# EEZ_DIB_DCM220_r2B3.net
KiCad netlist of a schematic drawn in EAGLE
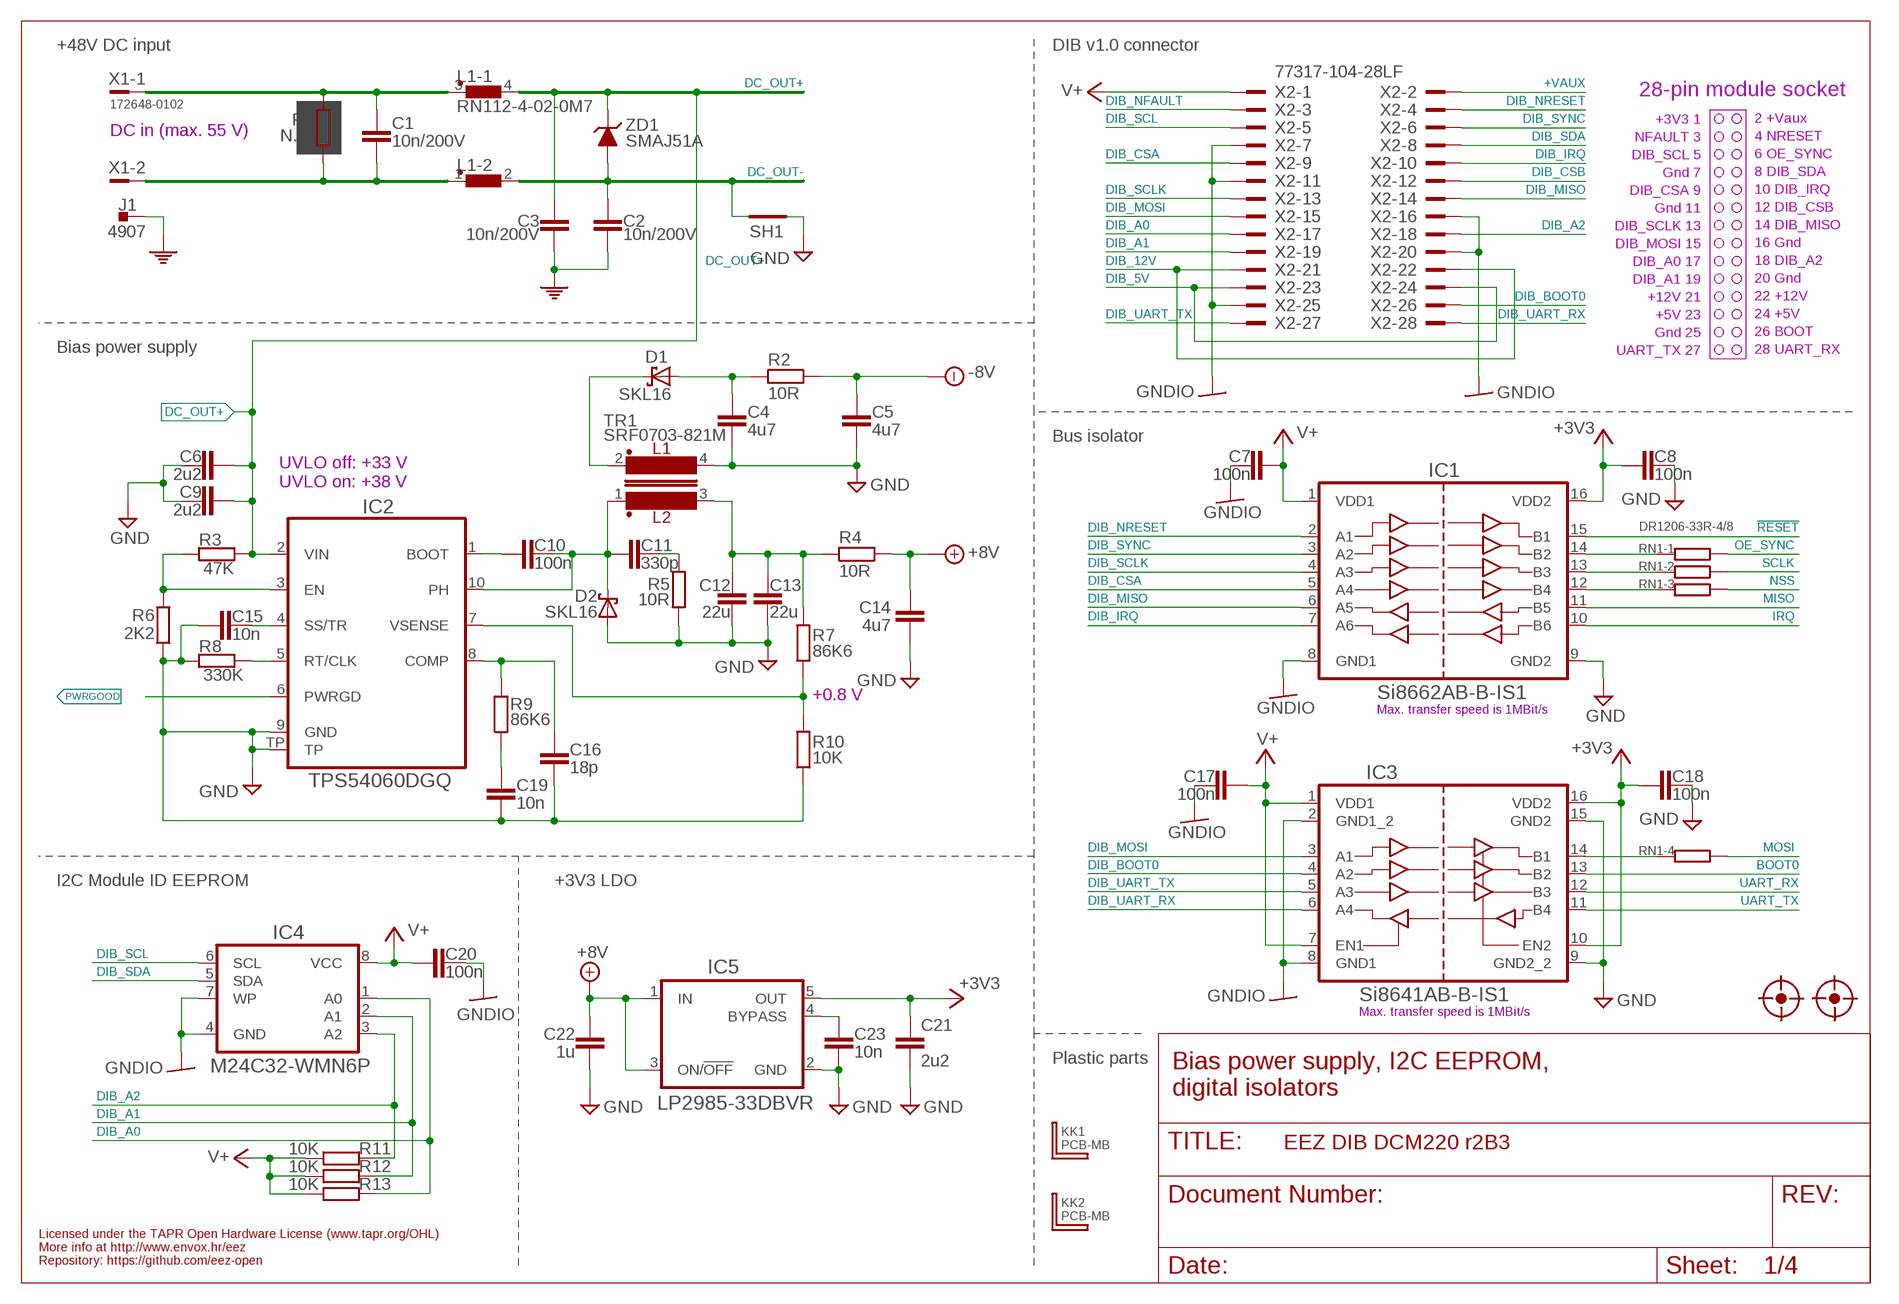
[diagram p0: schematic, sheet 1]
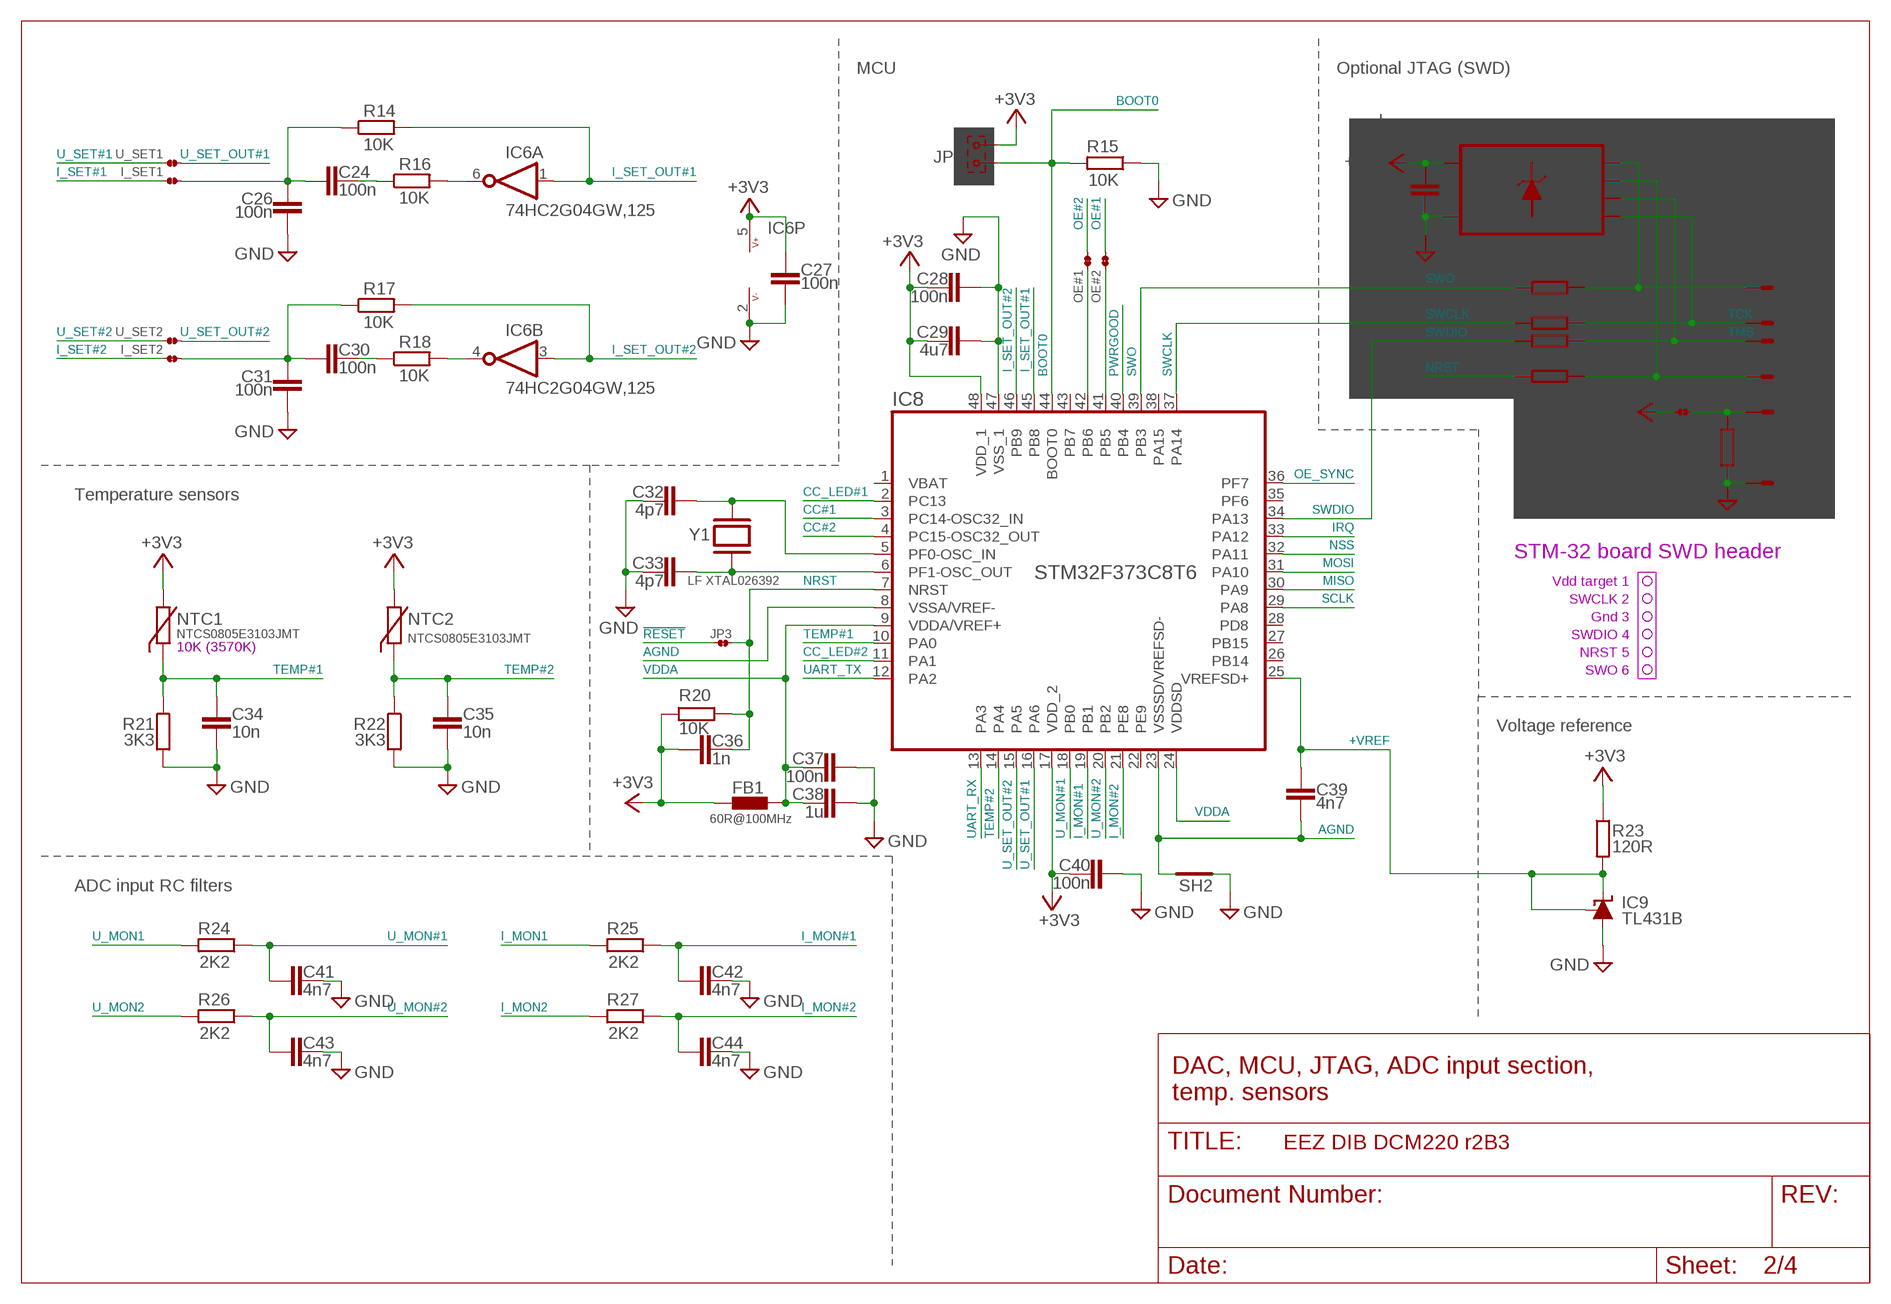
[diagram p1: schematic, sheet 2]
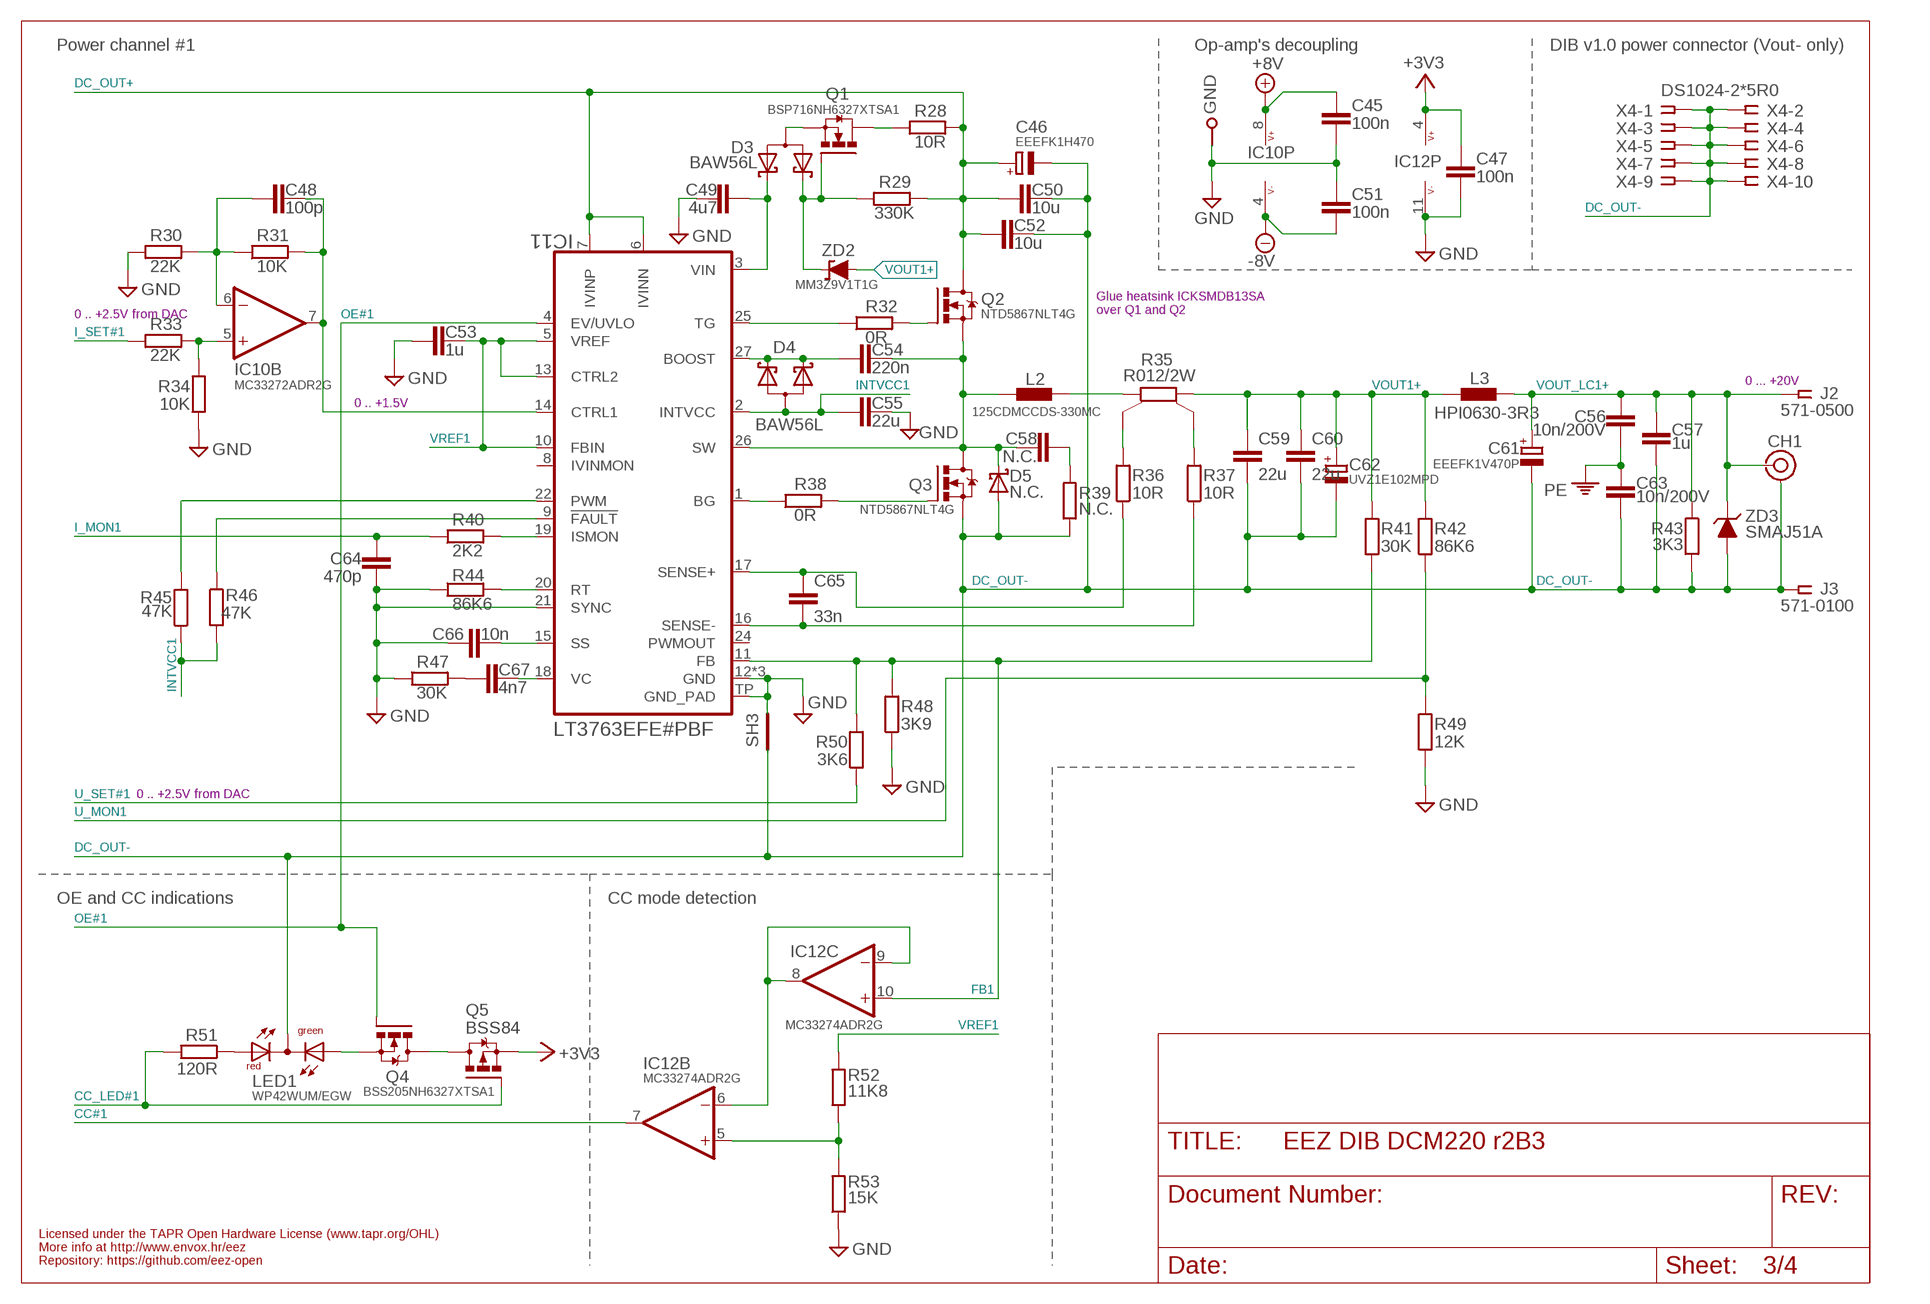
[diagram p2: schematic, sheet 3]
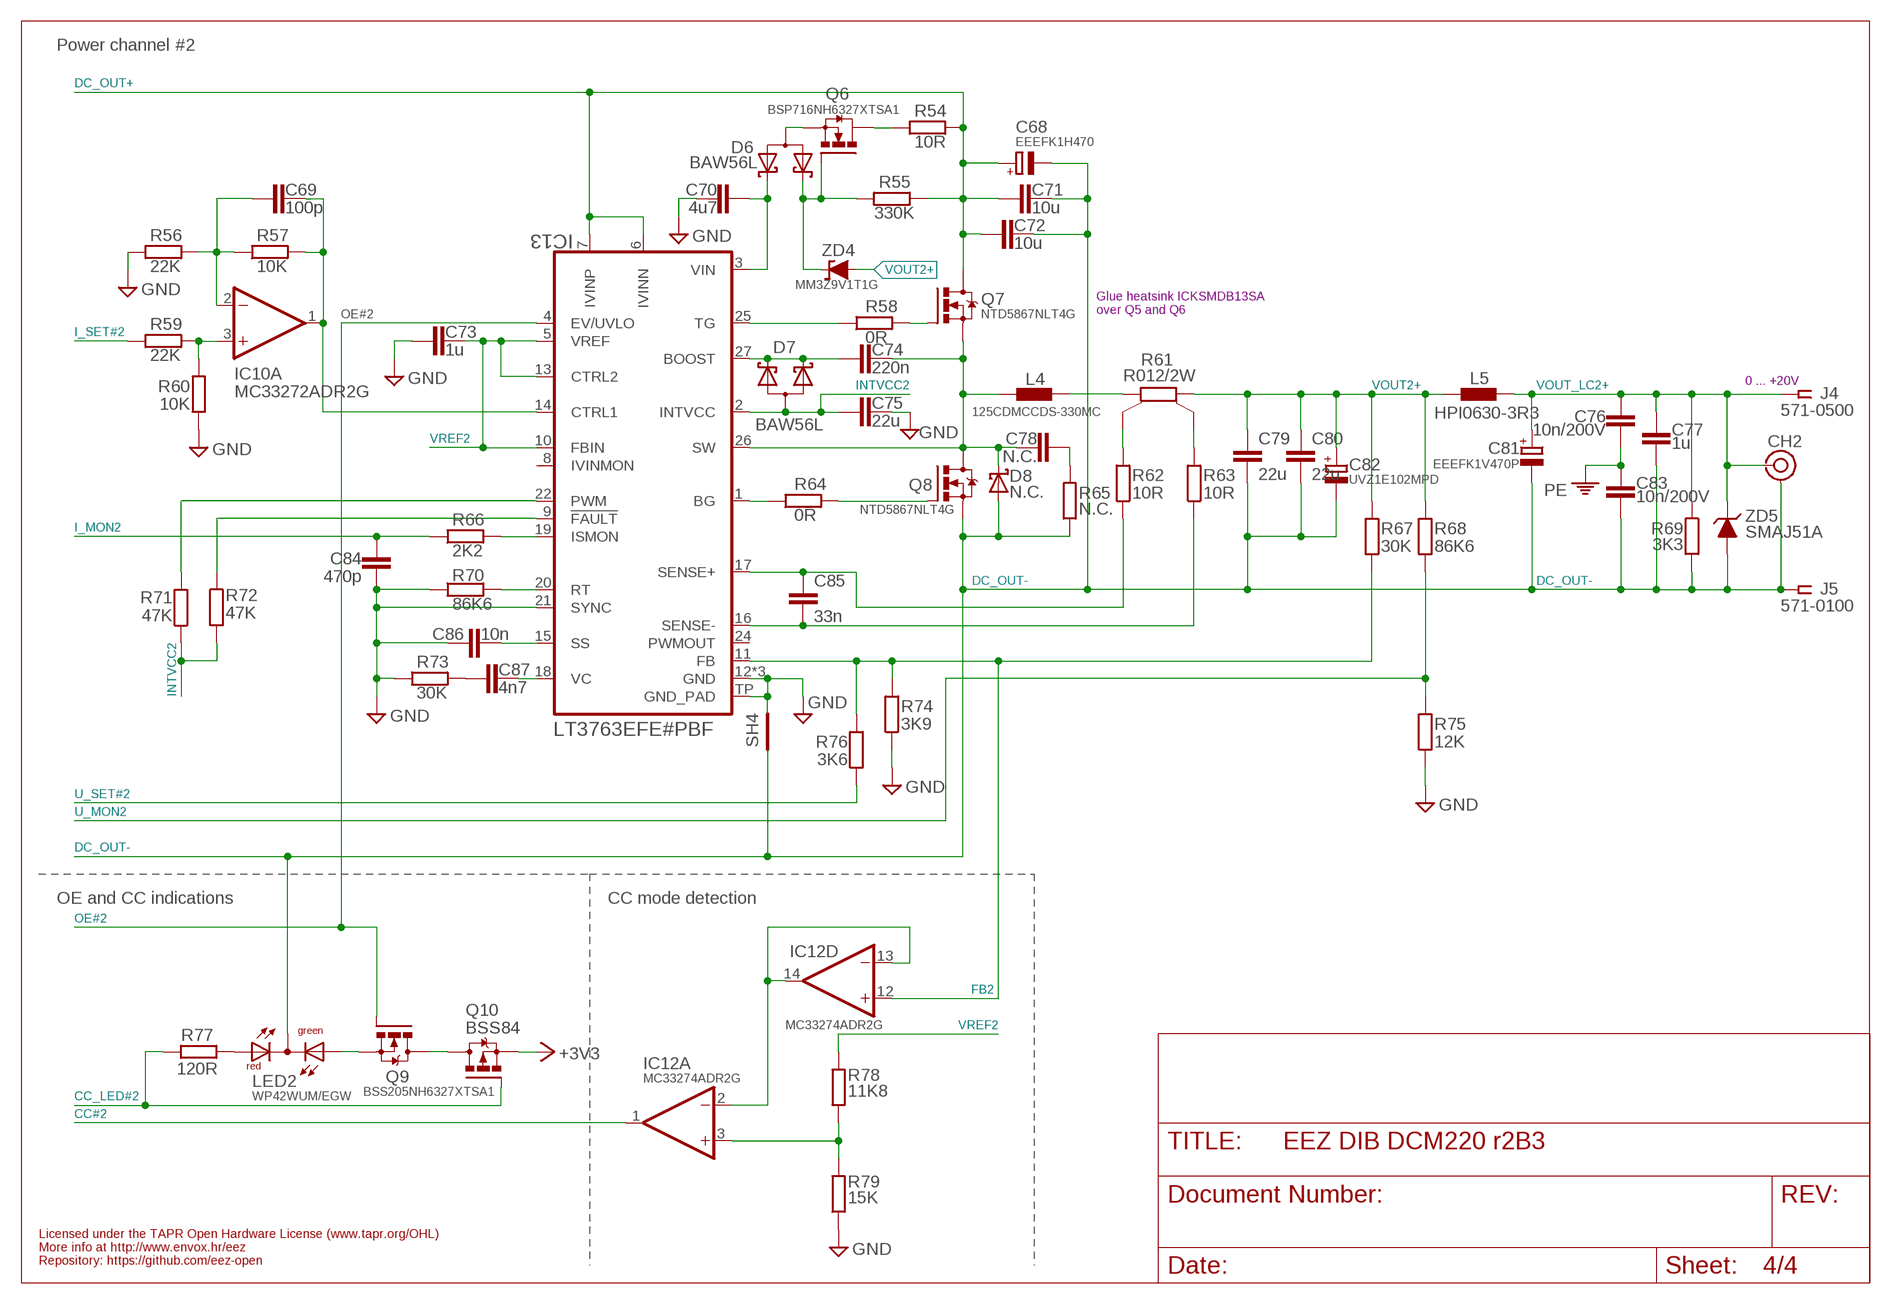
[diagram p3: schematic, sheet 4]

(export (version "E")
  (design (tool "Eeschema 10.0.6"))
  (components
    (comp (ref "C45")
      (value "100n")
      (footprint "eagle-import:C0603")
      (libsource (lib "eagle-import") (part "C-EUC0603"))
    )
    (comp (ref "C46")
      (value "EEEFK1H470")
      (footprint "eagle-import:CAPAE830X1050N")
      (libsource (lib "eagle-import") (part "ECAPSMD8.3MM/HA0"))
    )
    (comp (ref "C47")
      (value "100n")
      (footprint "eagle-import:C0603")
      (libsource (lib "eagle-import") (part "C-EUC0603"))
    )
    (comp (ref "C48")
      (value "100p")
      (footprint "eagle-import:C0805")
      (libsource (lib "eagle-import") (part "C-EUC0805"))
    )
    (comp (ref "C49")
      (value "4u7")
      (footprint "eagle-import:C1206")
      (libsource (lib "eagle-import") (part "C-EUC1206"))
    )
    (comp (ref "C50")
      (value "10u")
      (footprint "eagle-import:C1210")
      (libsource (lib "eagle-import") (part "C-EUC1210"))
    )
    (comp (ref "C51")
      (value "100n")
      (footprint "eagle-import:C0603")
      (libsource (lib "eagle-import") (part "C-EUC0603"))
    )
    (comp (ref "C52")
      (value "10u")
      (footprint "eagle-import:C1210")
      (libsource (lib "eagle-import") (part "C-EUC1210"))
    )
    (comp (ref "C53")
      (value "1u")
      (footprint "eagle-import:C0805")
      (libsource (lib "eagle-import") (part "C-EUC0805"))
    )
    (comp (ref "C54")
      (value "220n")
      (footprint "eagle-import:C0805")
      (libsource (lib "eagle-import") (part "C-EUC0805"))
    )
    (comp (ref "C55")
      (value "22u")
      (footprint "eagle-import:C1210")
      (libsource (lib "eagle-import") (part "C-EUC1210"))
    )
    (comp (ref "C56")
      (value "10n/200V")
      (footprint "eagle-import:C1206")
      (libsource (lib "eagle-import") (part "C-EUC1206"))
    )
    (comp (ref "C57")
      (value "1u")
      (footprint "eagle-import:C0805")
      (libsource (lib "eagle-import") (part "C-EUC0805"))
    )
    (comp (ref "C58")
      (value "N.C.")
      (footprint "eagle-import:C0805")
      (libsource (lib "eagle-import") (part "C-EUC0805"))
    )
    (comp (ref "C59")
      (value "22u")
      (footprint "eagle-import:C1210")
      (libsource (lib "eagle-import") (part "C-EUC1210"))
    )
    (comp (ref "C60")
      (value "22u")
      (footprint "eagle-import:C1210")
      (libsource (lib "eagle-import") (part "C-EUC1210"))
    )
    (comp (ref "C61")
      (value "EEEFK1V470P")
      (footprint "eagle-import:CAPAE660X610N")
      (libsource (lib "eagle-import") (part "ECAPPANASONIC_H"))
    )
    (comp (ref "C62")
      (value "UVZ1E102MPD")
      (footprint "eagle-import:ECAP5_10.5")
      (libsource (lib "eagle-import") (part "ECAP5G_10.5MM"))
    )
    (comp (ref "C63")
      (value "10n/200V")
      (footprint "eagle-import:C1206")
      (libsource (lib "eagle-import") (part "C-EUC1206"))
    )
    (comp (ref "C64")
      (value "470p")
      (footprint "eagle-import:C0805")
      (libsource (lib "eagle-import") (part "C-EUC0805"))
    )
    (comp (ref "C65")
      (value "33n")
      (footprint "eagle-import:C0805")
      (libsource (lib "eagle-import") (part "C-EUC0805"))
    )
    (comp (ref "C66")
      (value "10n")
      (footprint "eagle-import:C0805")
      (libsource (lib "eagle-import") (part "C-EUC0805"))
    )
    (comp (ref "C67")
      (value "4n7")
      (footprint "eagle-import:C0805")
      (libsource (lib "eagle-import") (part "C-EUC0805"))
    )
    (comp (ref "CH1")
      (value "TEST_POINT-2")
      (footprint "eagle-import:TP_1.1MM_2")
      (libsource (lib "eagle-import") (part "TEST_POINT-2"))
    )
    (comp (ref "D3")
      (value "BAW56L")
      (footprint "eagle-import:SOT23")
      (libsource (lib "eagle-import") (part "BAW56L"))
    )
    (comp (ref "D4")
      (value "BAW56L")
      (footprint "eagle-import:SOT23")
      (libsource (lib "eagle-import") (part "BAW56L"))
    )
    (comp (ref "D5")
      (value "N.C.")
      (footprint "eagle-import:SMA")
      (libsource (lib "eagle-import") (part "SCHOTTKYSMA_DO-214AC"))
    )
    (comp (ref "GND")
      (value "TEST-PIN_0.9MM")
      (footprint "eagle-import:TEST-PIN_0.9MM")
      (libsource (lib "eagle-import") (part "TEST-PIN_0.9MM"))
    )
    (comp (ref "IC10")
      (value "MC33272ADR2G")
      (footprint "eagle-import:SOIC127P600X173-8N")
      (libsource (lib "eagle-import") (part "TL072SOIC8"))
    )
    (comp (ref "IC11")
      (value "LT3763EFE#PBF")
      (footprint "eagle-import:LTC_05-08-1663-EB")
      (libsource (lib "eagle-import") (part "LT3763EFE#PBF"))
    )
    (comp (ref "IC12")
      (value "MC33274ADR2G")
      (footprint "eagle-import:SOIC127P600X175-14N")
      (fields (field (name "MPN") "TL074ACD"))
      (libsource (lib "eagle-import") (part "TL074SOIC14"))
    )
    (comp (ref "J2")
      (value "571-0500")
      (footprint "eagle-import:DELTRON_571")
      (libsource (lib "eagle-import") (part "571-0500"))
    )
    (comp (ref "J3")
      (value "571-0100")
      (footprint "eagle-import:DELTRON_571")
      (libsource (lib "eagle-import") (part "571-0100"))
    )
    (comp (ref "L2")
      (value "125CDMCCDS-330MC")
      (footprint "eagle-import:125CDMCC_DS")
      (libsource (lib "eagle-import") (part "125CDMCC/DS"))
    )
    (comp (ref "L3")
      (value "HPI0630-3R3")
      (footprint "eagle-import:COILCRAFT_HPI0630")
      (libsource (lib "eagle-import") (part "COILCRAFT_HPI0630"))
    )
    (comp (ref "LED1")
      (value "WP42WUM/EGW")
      (footprint "eagle-import:L-42WUM-1EGWT")
      (libsource (lib "eagle-import") (part "LED_L-42WUM/1EGWT"))
    )
    (comp (ref "Q1")
      (value "BSP716NH6327XTSA1")
      (footprint "eagle-import:SOT223")
      (libsource (lib "eagle-import") (part "N-HEXFET-2D_?-SOT232IRLL014N"))
    )
    (comp (ref "Q2")
      (value "NTD5867NLT4G")
      (footprint "eagle-import:TO229P990X239-3N")
      (libsource (lib "eagle-import") (part "N-MOSFETDPAK"))
    )
    (comp (ref "Q3")
      (value "NTD5867NLT4G")
      (footprint "eagle-import:TO229P990X239-3N")
      (libsource (lib "eagle-import") (part "N-MOSFETDPAK"))
    )
    (comp (ref "Q4")
      (value "BSS205NH6327XTSA1")
      (footprint "eagle-import:SOT103P240X110-3N")
      (fields (field (name "MPN") "2N7002-7-F"))
      (libsource (lib "eagle-import") (part "2N7002"))
    )
    (comp (ref "Q5")
      (value "BSS84")
      (footprint "eagle-import:SOT95P237X112-3N")
      (fields (field (name "MPN") "IRLML2246TRPBF"))
      (libsource (lib "eagle-import") (part "IRLML2246TRPBF"))
    )
    (comp (ref "R28")
      (value "10R")
      (footprint "eagle-import:R0805")
      (libsource (lib "eagle-import") (part "R-EU_R0805"))
    )
    (comp (ref "R29")
      (value "330K")
      (footprint "eagle-import:R0805")
      (libsource (lib "eagle-import") (part "R-EU_R0805"))
    )
    (comp (ref "R30")
      (value "22K")
      (footprint "eagle-import:R0805")
      (libsource (lib "eagle-import") (part "R-EU_R0805"))
    )
    (comp (ref "R31")
      (value "10K")
      (footprint "eagle-import:R0805")
      (libsource (lib "eagle-import") (part "R-EU_R0805"))
    )
    (comp (ref "R32")
      (value "0R")
      (footprint "eagle-import:R0805")
      (libsource (lib "eagle-import") (part "R-EU_R0805"))
    )
    (comp (ref "R33")
      (value "22K")
      (footprint "eagle-import:R0805")
      (libsource (lib "eagle-import") (part "R-EU_R0805"))
    )
    (comp (ref "R34")
      (value "10K")
      (footprint "eagle-import:R0805")
      (libsource (lib "eagle-import") (part "R-EU_R0805"))
    )
    (comp (ref "R35")
      (value "R012/2W")
      (footprint "eagle-import:R_2512-4WIRE")
      (libsource (lib "eagle-import") (part "R-EU_4WIRE2512"))
    )
    (comp (ref "R36")
      (value "10R")
      (footprint "eagle-import:R0805")
      (libsource (lib "eagle-import") (part "R-EU_R0805"))
    )
    (comp (ref "R37")
      (value "10R")
      (footprint "eagle-import:R0805")
      (libsource (lib "eagle-import") (part "R-EU_R0805"))
    )
    (comp (ref "R38")
      (value "0R")
      (footprint "eagle-import:R0805")
      (libsource (lib "eagle-import") (part "R-EU_R0805"))
    )
    (comp (ref "R39")
      (value "N.C.")
      (footprint "eagle-import:R1206")
      (libsource (lib "eagle-import") (part "R-EU_R1206"))
    )
    (comp (ref "R40")
      (value "2K2")
      (footprint "eagle-import:R0805")
      (libsource (lib "eagle-import") (part "R-EU_R0805"))
    )
    (comp (ref "R41")
      (value "30K")
      (footprint "eagle-import:R0805")
      (libsource (lib "eagle-import") (part "R-EU_R0805"))
    )
    (comp (ref "R42")
      (value "86K6")
      (footprint "eagle-import:R0805")
      (libsource (lib "eagle-import") (part "R-EU_R0805"))
    )
    (comp (ref "R43")
      (value "3K3")
      (footprint "eagle-import:R0805")
      (libsource (lib "eagle-import") (part "R-EU_R0805"))
    )
    (comp (ref "R44")
      (value "86K6")
      (footprint "eagle-import:R0805")
      (libsource (lib "eagle-import") (part "R-EU_R0805"))
    )
    (comp (ref "R45")
      (value "47K")
      (footprint "eagle-import:R0805")
      (libsource (lib "eagle-import") (part "R-EU_R0805"))
    )
    (comp (ref "R46")
      (value "47K")
      (footprint "eagle-import:R0805")
      (libsource (lib "eagle-import") (part "R-EU_R0805"))
    )
    (comp (ref "R47")
      (value "30K")
      (footprint "eagle-import:R0805")
      (libsource (lib "eagle-import") (part "R-EU_R0805"))
    )
    (comp (ref "R48")
      (value "3K9")
      (footprint "eagle-import:R0805")
      (libsource (lib "eagle-import") (part "R-EU_R0805"))
    )
    (comp (ref "R49")
      (value "12K")
      (footprint "eagle-import:R0805")
      (libsource (lib "eagle-import") (part "R-EU_R0805"))
    )
    (comp (ref "R50")
      (value "3K6")
      (footprint "eagle-import:R0805")
      (libsource (lib "eagle-import") (part "R-EU_R0805"))
    )
    (comp (ref "R51")
      (value "120R")
      (footprint "eagle-import:R0805")
      (libsource (lib "eagle-import") (part "R-EU_R0805"))
    )
    (comp (ref "R52")
      (value "11K8")
      (footprint "eagle-import:R0805")
      (libsource (lib "eagle-import") (part "R-EU_R0805"))
    )
    (comp (ref "R53")
      (value "15K")
      (footprint "eagle-import:R0805")
      (libsource (lib "eagle-import") (part "R-EU_R0805"))
    )
    (comp (ref "SH3")
      (value "SHORTNOHOLE")
      (footprint "eagle-import:SHORT_NOHOLE")
      (libsource (lib "eagle-import") (part "SHORTNOHOLE"))
    )
    (comp (ref "X4")
      (value "DS1024-2*5R0")
      (footprint "eagle-import:SSW-105-02-T-D-RA")
      (libsource (lib "eagle-import") (part "SSW-105-02-T-D-RA"))
    )
    (comp (ref "ZD2")
      (value "MM3Z9V1T1G")
      (footprint "eagle-import:SOD323-W")
      (libsource (lib "eagle-import") (part "ZENER-DIODESOD323"))
    )
    (comp (ref "ZD3")
      (value "SMAJ51A")
      (footprint "eagle-import:DO214AA")
      (libsource (lib "eagle-import") (part "P6SMB68A"))
    )
    (comp (ref "C68")
      (value "EEEFK1H470")
      (footprint "eagle-import:CAPAE830X1050N")
      (libsource (lib "eagle-import") (part "ECAPSMD8.3MM/HA0"))
    )
    (comp (ref "C69")
      (value "100p")
      (footprint "eagle-import:C0805")
      (libsource (lib "eagle-import") (part "C-EUC0805"))
    )
    (comp (ref "C70")
      (value "4u7")
      (footprint "eagle-import:C1206")
      (libsource (lib "eagle-import") (part "C-EUC1206"))
    )
    (comp (ref "C71")
      (value "10u")
      (footprint "eagle-import:C1210")
      (libsource (lib "eagle-import") (part "C-EUC1210"))
    )
    (comp (ref "C72")
      (value "10u")
      (footprint "eagle-import:C1210")
      (libsource (lib "eagle-import") (part "C-EUC1210"))
    )
    (comp (ref "C73")
      (value "1u")
      (footprint "eagle-import:C0805")
      (libsource (lib "eagle-import") (part "C-EUC0805"))
    )
    (comp (ref "C74")
      (value "220n")
      (footprint "eagle-import:C0805")
      (libsource (lib "eagle-import") (part "C-EUC0805"))
    )
    (comp (ref "C75")
      (value "22u")
      (footprint "eagle-import:C1210")
      (libsource (lib "eagle-import") (part "C-EUC1210"))
    )
    (comp (ref "C76")
      (value "10n/200V")
      (footprint "eagle-import:C1206")
      (libsource (lib "eagle-import") (part "C-EUC1206"))
    )
    (comp (ref "C77")
      (value "1u")
      (footprint "eagle-import:C0805")
      (libsource (lib "eagle-import") (part "C-EUC0805"))
    )
    (comp (ref "C78")
      (value "N.C.")
      (footprint "eagle-import:C0805")
      (libsource (lib "eagle-import") (part "C-EUC0805"))
    )
    (comp (ref "C79")
      (value "22u")
      (footprint "eagle-import:C1210")
      (libsource (lib "eagle-import") (part "C-EUC1210"))
    )
    (comp (ref "C80")
      (value "22u")
      (footprint "eagle-import:C1210")
      (libsource (lib "eagle-import") (part "C-EUC1210"))
    )
    (comp (ref "C81")
      (value "EEEFK1V470P")
      (footprint "eagle-import:CAPAE660X610N")
      (libsource (lib "eagle-import") (part "ECAPPANASONIC_H"))
    )
    (comp (ref "C82")
      (value "UVZ1E102MPD")
      (footprint "eagle-import:ECAP5_10.5")
      (libsource (lib "eagle-import") (part "ECAP5G_10.5MM"))
    )
    (comp (ref "C83")
      (value "10n/200V")
      (footprint "eagle-import:C1206")
      (libsource (lib "eagle-import") (part "C-EUC1206"))
    )
    (comp (ref "C84")
      (value "470p")
      (footprint "eagle-import:C0805")
      (libsource (lib "eagle-import") (part "C-EUC0805"))
    )
    (comp (ref "C85")
      (value "33n")
      (footprint "eagle-import:C0805")
      (libsource (lib "eagle-import") (part "C-EUC0805"))
    )
    (comp (ref "C86")
      (value "10n")
      (footprint "eagle-import:C0805")
      (libsource (lib "eagle-import") (part "C-EUC0805"))
    )
    (comp (ref "C87")
      (value "4n7")
      (footprint "eagle-import:C0805")
      (libsource (lib "eagle-import") (part "C-EUC0805"))
    )
    (comp (ref "CH2")
      (value "TEST_POINT-2")
      (footprint "eagle-import:TP_1.1MM_2")
      (libsource (lib "eagle-import") (part "TEST_POINT-2"))
    )
    (comp (ref "D6")
      (value "BAW56L")
      (footprint "eagle-import:SOT23")
      (libsource (lib "eagle-import") (part "BAW56L"))
    )
    (comp (ref "D7")
      (value "BAW56L")
      (footprint "eagle-import:SOT23")
      (libsource (lib "eagle-import") (part "BAW56L"))
    )
    (comp (ref "D8")
      (value "N.C.")
      (footprint "eagle-import:SMA")
      (libsource (lib "eagle-import") (part "SCHOTTKYSMA_DO-214AC"))
    )
    (comp (ref "IC13")
      (value "LT3763EFE#PBF")
      (footprint "eagle-import:LTC_05-08-1663-EB")
      (libsource (lib "eagle-import") (part "LT3763EFE#PBF"))
    )
    (comp (ref "J4")
      (value "571-0500")
      (footprint "eagle-import:DELTRON_571")
      (libsource (lib "eagle-import") (part "571-0500"))
    )
    (comp (ref "J5")
      (value "571-0100")
      (footprint "eagle-import:DELTRON_571")
      (libsource (lib "eagle-import") (part "571-0100"))
    )
    (comp (ref "L4")
      (value "125CDMCCDS-330MC")
      (footprint "eagle-import:125CDMCC_DS")
      (libsource (lib "eagle-import") (part "125CDMCC/DS"))
    )
    (comp (ref "L5")
      (value "HPI0630-3R3")
      (footprint "eagle-import:COILCRAFT_HPI0630")
      (libsource (lib "eagle-import") (part "COILCRAFT_HPI0630"))
    )
    (comp (ref "LED2")
      (value "WP42WUM/EGW")
      (footprint "eagle-import:L-42WUM-1EGWT")
      (libsource (lib "eagle-import") (part "LED_L-42WUM/1EGWT"))
    )
    (comp (ref "Q6")
      (value "BSP716NH6327XTSA1")
      (footprint "eagle-import:SOT223")
      (libsource (lib "eagle-import") (part "N-HEXFET-2D_?-SOT232IRLL014N"))
    )
    (comp (ref "Q7")
      (value "NTD5867NLT4G")
      (footprint "eagle-import:TO229P990X239-3N")
      (libsource (lib "eagle-import") (part "N-MOSFETDPAK"))
    )
    (comp (ref "Q8")
      (value "NTD5867NLT4G")
      (footprint "eagle-import:TO229P990X239-3N")
      (libsource (lib "eagle-import") (part "N-MOSFETDPAK"))
    )
    (comp (ref "Q9")
      (value "BSS205NH6327XTSA1")
      (footprint "eagle-import:SOT103P240X110-3N")
      (fields (field (name "MPN") "2N7002-7-F"))
      (libsource (lib "eagle-import") (part "2N7002"))
    )
    (comp (ref "Q10")
      (value "BSS84")
      (footprint "eagle-import:SOT95P237X112-3N")
      (fields (field (name "MPN") "IRLML2246TRPBF"))
      (libsource (lib "eagle-import") (part "IRLML2246TRPBF"))
    )
    (comp (ref "R54")
      (value "10R")
      (footprint "eagle-import:R0805")
      (libsource (lib "eagle-import") (part "R-EU_R0805"))
    )
    (comp (ref "R55")
      (value "330K")
      (footprint "eagle-import:R0805")
      (libsource (lib "eagle-import") (part "R-EU_R0805"))
    )
    (comp (ref "R56")
      (value "22K")
      (footprint "eagle-import:R0805")
      (libsource (lib "eagle-import") (part "R-EU_R0805"))
    )
    (comp (ref "R57")
      (value "10K")
      (footprint "eagle-import:R0805")
      (libsource (lib "eagle-import") (part "R-EU_R0805"))
    )
    (comp (ref "R58")
      (value "0R")
      (footprint "eagle-import:R0805")
      (libsource (lib "eagle-import") (part "R-EU_R0805"))
    )
    (comp (ref "R59")
      (value "22K")
      (footprint "eagle-import:R0805")
      (libsource (lib "eagle-import") (part "R-EU_R0805"))
    )
    (comp (ref "R60")
      (value "10K")
      (footprint "eagle-import:R0805")
      (libsource (lib "eagle-import") (part "R-EU_R0805"))
    )
    (comp (ref "R61")
      (value "R012/2W")
      (footprint "eagle-import:R_2512-4WIRE")
      (libsource (lib "eagle-import") (part "R-EU_4WIRE2512"))
    )
    (comp (ref "R62")
      (value "10R")
      (footprint "eagle-import:R0805")
      (libsource (lib "eagle-import") (part "R-EU_R0805"))
    )
    (comp (ref "R63")
      (value "10R")
      (footprint "eagle-import:R0805")
      (libsource (lib "eagle-import") (part "R-EU_R0805"))
    )
    (comp (ref "R64")
      (value "0R")
      (footprint "eagle-import:R0805")
      (libsource (lib "eagle-import") (part "R-EU_R0805"))
    )
    (comp (ref "R65")
      (value "N.C.")
      (footprint "eagle-import:R1206")
      (libsource (lib "eagle-import") (part "R-EU_R1206"))
    )
    (comp (ref "R66")
      (value "2K2")
      (footprint "eagle-import:R0805")
      (libsource (lib "eagle-import") (part "R-EU_R0805"))
    )
    (comp (ref "R67")
      (value "30K")
      (footprint "eagle-import:R0805")
      (libsource (lib "eagle-import") (part "R-EU_R0805"))
    )
    (comp (ref "R68")
      (value "86K6")
      (footprint "eagle-import:R0805")
      (libsource (lib "eagle-import") (part "R-EU_R0805"))
    )
    (comp (ref "R69")
      (value "3K3")
      (footprint "eagle-import:R0805")
      (libsource (lib "eagle-import") (part "R-EU_R0805"))
    )
    (comp (ref "R70")
      (value "86K6")
      (footprint "eagle-import:R0805")
      (libsource (lib "eagle-import") (part "R-EU_R0805"))
    )
    (comp (ref "R71")
      (value "47K")
      (footprint "eagle-import:R0805")
      (libsource (lib "eagle-import") (part "R-EU_R0805"))
    )
    (comp (ref "R72")
      (value "47K")
      (footprint "eagle-import:R0805")
      (libsource (lib "eagle-import") (part "R-EU_R0805"))
    )
    (comp (ref "R73")
      (value "30K")
      (footprint "eagle-import:R0805")
      (libsource (lib "eagle-import") (part "R-EU_R0805"))
    )
    (comp (ref "R74")
      (value "3K9")
      (footprint "eagle-import:R0805")
      (libsource (lib "eagle-import") (part "R-EU_R0805"))
    )
    (comp (ref "R75")
      (value "12K")
      (footprint "eagle-import:R0805")
      (libsource (lib "eagle-import") (part "R-EU_R0805"))
    )
    (comp (ref "R76")
      (value "3K6")
      (footprint "eagle-import:R0805")
      (libsource (lib "eagle-import") (part "R-EU_R0805"))
    )
    (comp (ref "R77")
      (value "120R")
      (footprint "eagle-import:R0805")
      (libsource (lib "eagle-import") (part "R-EU_R0805"))
    )
    (comp (ref "R78")
      (value "11K8")
      (footprint "eagle-import:R0805")
      (libsource (lib "eagle-import") (part "R-EU_R0805"))
    )
    (comp (ref "R79")
      (value "15K")
      (footprint "eagle-import:R0805")
      (libsource (lib "eagle-import") (part "R-EU_R0805"))
    )
    (comp (ref "SH4")
      (value "SHORTNOHOLE")
      (footprint "eagle-import:SHORT_NOHOLE")
      (libsource (lib "eagle-import") (part "SHORTNOHOLE"))
    )
    (comp (ref "ZD4")
      (value "MM3Z9V1T1G")
      (footprint "eagle-import:SOD323-W")
      (libsource (lib "eagle-import") (part "ZENER-DIODESOD323"))
    )
    (comp (ref "ZD5")
      (value "SMAJ51A")
      (footprint "eagle-import:DO214AA")
      (libsource (lib "eagle-import") (part "P6SMB68A"))
    )
    (comp (ref "C24")
      (value "100n")
      (footprint "eagle-import:C0603")
      (libsource (lib "eagle-import") (part "C-EUC0603"))
    )
    (comp (ref "C25")
      (value "N.C.")
      (footprint "eagle-import:C0603")
      (libsource (lib "eagle-import") (part "C-EUC0603"))
    )
    (comp (ref "C26")
      (value "100n")
      (footprint "eagle-import:C0603")
      (libsource (lib "eagle-import") (part "C-EUC0603"))
    )
    (comp (ref "C27")
      (value "100n")
      (footprint "eagle-import:C0603")
      (libsource (lib "eagle-import") (part "C-EUC0603"))
    )
    (comp (ref "C28")
      (value "100n")
      (footprint "eagle-import:C0603")
      (libsource (lib "eagle-import") (part "C-EUC0603"))
    )
    (comp (ref "C29")
      (value "4u7")
      (footprint "eagle-import:C1206")
      (libsource (lib "eagle-import") (part "C-EUC1206"))
    )
    (comp (ref "C30")
      (value "100n")
      (footprint "eagle-import:C0603")
      (libsource (lib "eagle-import") (part "C-EUC0603"))
    )
    (comp (ref "C31")
      (value "100n")
      (footprint "eagle-import:C0603")
      (libsource (lib "eagle-import") (part "C-EUC0603"))
    )
    (comp (ref "C32")
      (value "4p7")
      (footprint "eagle-import:C0603")
      (libsource (lib "eagle-import") (part "C-EUC0603"))
    )
    (comp (ref "C33")
      (value "4p7")
      (footprint "eagle-import:C0603")
      (libsource (lib "eagle-import") (part "C-EUC0603"))
    )
    (comp (ref "C34")
      (value "10n")
      (footprint "eagle-import:C0805")
      (libsource (lib "eagle-import") (part "C-EUC0805"))
    )
    (comp (ref "C35")
      (value "10n")
      (footprint "eagle-import:C0805")
      (libsource (lib "eagle-import") (part "C-EUC0805"))
    )
    (comp (ref "C36")
      (value "1n")
      (footprint "eagle-import:C0805")
      (libsource (lib "eagle-import") (part "C-EUC0805"))
    )
    (comp (ref "C37")
      (value "100n")
      (footprint "eagle-import:C0603")
      (libsource (lib "eagle-import") (part "C-EUC0603"))
    )
    (comp (ref "C38")
      (value "1u")
      (footprint "eagle-import:C0805")
      (libsource (lib "eagle-import") (part "C-EUC0805"))
    )
    (comp (ref "C39")
      (value "4n7")
      (footprint "eagle-import:C0805")
      (libsource (lib "eagle-import") (part "C-EUC0805"))
    )
    (comp (ref "C40")
      (value "100n")
      (footprint "eagle-import:C0603")
      (libsource (lib "eagle-import") (part "C-EUC0603"))
    )
    (comp (ref "C41")
      (value "4n7")
      (footprint "eagle-import:C0805")
      (libsource (lib "eagle-import") (part "C-EUC0805"))
    )
    (comp (ref "C42")
      (value "4n7")
      (footprint "eagle-import:C0805")
      (libsource (lib "eagle-import") (part "C-EUC0805"))
    )
    (comp (ref "C43")
      (value "4n7")
      (footprint "eagle-import:C0805")
      (libsource (lib "eagle-import") (part "C-EUC0805"))
    )
    (comp (ref "C44")
      (value "4n7")
      (footprint "eagle-import:C0805")
      (libsource (lib "eagle-import") (part "C-EUC0805"))
    )
    (comp (ref "FB1")
      (value "60R@100MHz")
      (footprint "eagle-import:BEAD0603")
      (libsource (lib "eagle-import") (part "FERRITE_BEAD0603"))
    )
    (comp (ref "IC6")
      (value "74HC2G04GW,125")
      (footprint "eagle-import:SOT65P210X110-6N")
      (libsource (lib "eagle-import") (part "74HC2G04"))
    )
    (comp (ref "IC7")
      (value "N.C.")
      (footprint "eagle-import:DRL6")
      (libsource (lib "eagle-import") (part "TPD4E001-DRL"))
    )
    (comp (ref "IC8")
      (value "STM32F373C8T6")
      (footprint "eagle-import:LQFP-48")
      (libsource (lib "eagle-import") (part "STM32F373C8T6"))
    )
    (comp (ref "IC9")
      (value "TL431B")
      (footprint "eagle-import:SOT103P240X110-3N")
      (libsource (lib "eagle-import") (part "TL431"))
    )
    (comp (ref "I_SET1")
      (value "JP2-NOCUT")
      (footprint "eagle-import:JP2-NOCUT")
      (libsource (lib "eagle-import") (part "JP2-NOCUT"))
    )
    (comp (ref "I_SET2")
      (value "JP2-NOCUT")
      (footprint "eagle-import:JP2-NOCUT")
      (libsource (lib "eagle-import") (part "JP2-NOCUT"))
    )
    (comp (ref "JP1")
      (value "JUMPER-2PIN-2MM")
      (footprint "eagle-import:2MM-2")
      (libsource (lib "eagle-import") (part "JUMPER-2PIN-2MM"))
    )
    (comp (ref "JP2")
      (value "JP2-CUT")
      (footprint "eagle-import:JP2-CUT")
      (libsource (lib "eagle-import") (part "JP2-CUT"))
    )
    (comp (ref "JP3")
      (value "JP2-NOCUT")
      (footprint "eagle-import:JP2-NOCUT")
      (libsource (lib "eagle-import") (part "JP2-NOCUT"))
    )
    (comp (ref "NTC1")
      (value "NTCS0805E3103JMT")
      (footprint "eagle-import:R_0805")
      (libsource (lib "eagle-import") (part "NTCR_0805"))
    )
    (comp (ref "NTC2")
      (value "NTCS0805E3103JMT")
      (footprint "eagle-import:R_0805")
      (libsource (lib "eagle-import") (part "NTCR_0805"))
    )
    (comp (ref "OE#1")
      (value "JP2-NOCUT")
      (footprint "eagle-import:JP2-NOCUT")
      (libsource (lib "eagle-import") (part "JP2-NOCUT"))
    )
    (comp (ref "OE#2")
      (value "JP2-NOCUT")
      (footprint "eagle-import:JP2-NOCUT")
      (libsource (lib "eagle-import") (part "JP2-NOCUT"))
    )
    (comp (ref "R14")
      (value "10K")
      (footprint "eagle-import:R0805")
      (libsource (lib "eagle-import") (part "R-EU_R0805"))
    )
    (comp (ref "R15")
      (value "10K")
      (footprint "eagle-import:R0805")
      (libsource (lib "eagle-import") (part "R-EU_R0805"))
    )
    (comp (ref "R16")
      (value "10K")
      (footprint "eagle-import:R0805")
      (libsource (lib "eagle-import") (part "R-EU_R0805"))
    )
    (comp (ref "R17")
      (value "10K")
      (footprint "eagle-import:R0805")
      (libsource (lib "eagle-import") (part "R-EU_R0805"))
    )
    (comp (ref "R18")
      (value "10K")
      (footprint "eagle-import:R0805")
      (libsource (lib "eagle-import") (part "R-EU_R0805"))
    )
    (comp (ref "R19")
      (value "N.C.")
      (footprint "eagle-import:R0805")
      (libsource (lib "eagle-import") (part "R-EU_R0805"))
    )
    (comp (ref "R20")
      (value "10K")
      (footprint "eagle-import:R0805")
      (libsource (lib "eagle-import") (part "R-EU_R0805"))
    )
    (comp (ref "R21")
      (value "3K3")
      (footprint "eagle-import:R0805")
      (libsource (lib "eagle-import") (part "R-EU_R0805"))
    )
    (comp (ref "R22")
      (value "3K3")
      (footprint "eagle-import:R0805")
      (libsource (lib "eagle-import") (part "R-EU_R0805"))
    )
    (comp (ref "R23")
      (value "120R")
      (footprint "eagle-import:R0805")
      (libsource (lib "eagle-import") (part "R-EU_R0805"))
    )
    (comp (ref "R24")
      (value "2K2")
      (footprint "eagle-import:R0805")
      (libsource (lib "eagle-import") (part "R-EU_R0805"))
    )
    (comp (ref "R25")
      (value "2K2")
      (footprint "eagle-import:R0805")
      (libsource (lib "eagle-import") (part "R-EU_R0805"))
    )
    (comp (ref "R26")
      (value "2K2")
      (footprint "eagle-import:R0805")
      (libsource (lib "eagle-import") (part "R-EU_R0805"))
    )
    (comp (ref "R27")
      (value "2K2")
      (footprint "eagle-import:R0805")
      (libsource (lib "eagle-import") (part "R-EU_R0805"))
    )
    (comp (ref "RN2")
      (value "N.C.")
      (footprint "eagle-import:CAY16")
      (libsource (lib "eagle-import") (part "R_ARRAY4"))
    )
    (comp (ref "SH2")
      (value "SHORTNOHOLE")
      (footprint "eagle-import:SHORT_NOHOLE")
      (libsource (lib "eagle-import") (part "SHORTNOHOLE"))
    )
    (comp (ref "U_SET1")
      (value "JP2-NOCUT")
      (footprint "eagle-import:JP2-NOCUT")
      (libsource (lib "eagle-import") (part "JP2-NOCUT"))
    )
    (comp (ref "U_SET2")
      (value "JP2-NOCUT")
      (footprint "eagle-import:JP2-NOCUT")
      (libsource (lib "eagle-import") (part "JP2-NOCUT"))
    )
    (comp (ref "X3")
      (value "N.C.")
      (footprint "eagle-import:22-23-2061")
      (fields (field (name "MF") "MOLEX") (field (name "MPN") "22-23-2061"))
      (libsource (lib "eagle-import") (part "22-23-2061"))
    )
    (comp (ref "Y1")
      (value "LF XTAL026392")
      (footprint "eagle-import:12SMX(B)")
      (libsource (lib "eagle-import") (part "XTAL7.5X5.1-B"))
    )
    (comp (ref "C1")
      (value "10n/200V")
      (footprint "eagle-import:C1206")
      (libsource (lib "eagle-import") (part "C-EUC1206"))
    )
    (comp (ref "C2")
      (value "10n/200V")
      (footprint "eagle-import:C1206")
      (libsource (lib "eagle-import") (part "C-EUC1206"))
    )
    (comp (ref "C3")
      (value "10n/200V")
      (footprint "eagle-import:C1206")
      (libsource (lib "eagle-import") (part "C-EUC1206"))
    )
    (comp (ref "C4")
      (value "4u7")
      (footprint "eagle-import:C1206")
      (libsource (lib "eagle-import") (part "C-EUC1206"))
    )
    (comp (ref "C5")
      (value "4u7")
      (footprint "eagle-import:C1206")
      (libsource (lib "eagle-import") (part "C-EUC1206"))
    )
    (comp (ref "C6")
      (value "2u2")
      (footprint "eagle-import:C1206")
      (libsource (lib "eagle-import") (part "C-EUC1206"))
    )
    (comp (ref "C7")
      (value "100n")
      (footprint "eagle-import:C0603")
      (libsource (lib "eagle-import") (part "C-EUC0603"))
    )
    (comp (ref "C8")
      (value "100n")
      (footprint "eagle-import:C0603")
      (libsource (lib "eagle-import") (part "C-EUC0603"))
    )
    (comp (ref "C9")
      (value "2u2")
      (footprint "eagle-import:C1206")
      (libsource (lib "eagle-import") (part "C-EUC1206"))
    )
    (comp (ref "C10")
      (value "100n")
      (footprint "eagle-import:C0603")
      (libsource (lib "eagle-import") (part "C-EUC0603"))
    )
    (comp (ref "C11")
      (value "330p")
      (footprint "eagle-import:C0805")
      (libsource (lib "eagle-import") (part "C-EUC0805"))
    )
    (comp (ref "C12")
      (value "22u")
      (footprint "eagle-import:C1206")
      (libsource (lib "eagle-import") (part "C-EUC1206"))
    )
    (comp (ref "C13")
      (value "22u")
      (footprint "eagle-import:C1206")
      (libsource (lib "eagle-import") (part "C-EUC1206"))
    )
    (comp (ref "C14")
      (value "4u7")
      (footprint "eagle-import:C1206")
      (libsource (lib "eagle-import") (part "C-EUC1206"))
    )
    (comp (ref "C15")
      (value "10n")
      (footprint "eagle-import:C0805")
      (libsource (lib "eagle-import") (part "C-EUC0805"))
    )
    (comp (ref "C16")
      (value "18p")
      (footprint "eagle-import:C0603")
      (libsource (lib "eagle-import") (part "C-EUC0603"))
    )
    (comp (ref "C17")
      (value "100n")
      (footprint "eagle-import:C0603")
      (libsource (lib "eagle-import") (part "C-EUC0603"))
    )
    (comp (ref "C18")
      (value "100n")
      (footprint "eagle-import:C0603")
      (libsource (lib "eagle-import") (part "C-EUC0603"))
    )
    (comp (ref "C19")
      (value "10n")
      (footprint "eagle-import:C0805")
      (libsource (lib "eagle-import") (part "C-EUC0805"))
    )
    (comp (ref "C20")
      (value "100n")
      (footprint "eagle-import:C0603")
      (libsource (lib "eagle-import") (part "C-EUC0603"))
    )
    (comp (ref "C21")
      (value "2u2")
      (footprint "eagle-import:C1206")
      (libsource (lib "eagle-import") (part "C-EUC1206"))
    )
    (comp (ref "C22")
      (value "1u")
      (footprint "eagle-import:C0805")
      (libsource (lib "eagle-import") (part "C-EUC0805"))
    )
    (comp (ref "C23")
      (value "10n")
      (footprint "eagle-import:C0805")
      (libsource (lib "eagle-import") (part "C-EUC0805"))
    )
    (comp (ref "D1")
      (value "SKL16")
      (footprint "eagle-import:SOD123")
      (libsource (lib "eagle-import") (part "SCHOTTKYSOD123"))
    )
    (comp (ref "D2")
      (value "SKL16")
      (footprint "eagle-import:SOD123")
      (libsource (lib "eagle-import") (part "SCHOTTKYSOD123"))
    )
    (comp (ref "FM1")
      (value "FIDUCIAL_2")
      (footprint "eagle-import:FIDUCIAL_DUAL")
      (libsource (lib "eagle-import") (part "FIDUCIAL_2"))
    )
    (comp (ref "FM2")
      (value "FIDUCIAL_2")
      (footprint "eagle-import:FIDUCIAL_DUAL")
      (libsource (lib "eagle-import") (part "FIDUCIAL_2"))
    )
    (comp (ref "IC1")
      (value "Si8662AB-B-IS1")
      (footprint "eagle-import:SOIC-16")
      (libsource (lib "eagle-import") (part "SI8662NSOIC-16"))
    )
    (comp (ref "IC2")
      (value "TPS54060DGQ")
      (footprint "eagle-import:SOP50P490X110-11N")
      (fields (field (name "MPN") "TPS54060ADGQ"))
      (libsource (lib "eagle-import") (part "TPS54060DGQ"))
    )
    (comp (ref "IC3")
      (value "Si8641AB-B-IS1")
      (footprint "eagle-import:SOIC-16")
      (libsource (lib "eagle-import") (part "SI8641NSOIC-16"))
    )
    (comp (ref "IC4")
      (value "M24C32-WMN6P")
      (footprint "eagle-import:SOIC127P600X173-8N")
      (libsource (lib "eagle-import") (part "AT24CXXSOIC8"))
    )
    (comp (ref "IC5")
      (value "LP2985-33DBVR")
      (footprint "eagle-import:SOT95P270X145-5N")
      (libsource (lib "eagle-import") (part "LP2985"))
    )
    (comp (ref "J1")
      (value "4907")
      (footprint "eagle-import:PCB_TAB-4907")
      (libsource (lib "eagle-import") (part "PCB_TAB-4907"))
    )
    (comp (ref "KK1")
      (value "PCB-MB")
      (footprint "eagle-import:PCB-MB")
      (libsource (lib "eagle-import") (part "PCB-MB"))
    )
    (comp (ref "KK2")
      (value "PCB-MB")
      (footprint "eagle-import:PCB-MB")
      (libsource (lib "eagle-import") (part "PCB-MB"))
    )
    (comp (ref "L1")
      (value "RN112-4-02-0M7")
      (footprint "eagle-import:RN112")
      (libsource (lib "eagle-import") (part "RN112"))
    )
    (comp (ref "R1")
      (value "N.C.")
      (footprint "eagle-import:R2512")
      (libsource (lib "eagle-import") (part "R-EU_R2512"))
    )
    (comp (ref "R2")
      (value "10R")
      (footprint "eagle-import:R0805")
      (libsource (lib "eagle-import") (part "R-EU_R0805"))
    )
    (comp (ref "R3")
      (value "47K")
      (footprint "eagle-import:R0805")
      (libsource (lib "eagle-import") (part "R-EU_R0805"))
    )
    (comp (ref "R4")
      (value "10R")
      (footprint "eagle-import:R0805")
      (libsource (lib "eagle-import") (part "R-EU_R0805"))
    )
    (comp (ref "R5")
      (value "10R")
      (footprint "eagle-import:R0805")
      (libsource (lib "eagle-import") (part "R-EU_R0805"))
    )
    (comp (ref "R6")
      (value "2K2")
      (footprint "eagle-import:R0805")
      (libsource (lib "eagle-import") (part "R-EU_R0805"))
    )
    (comp (ref "R7")
      (value "86K6")
      (footprint "eagle-import:R0805")
      (libsource (lib "eagle-import") (part "R-EU_R0805"))
    )
    (comp (ref "R8")
      (value "330K")
      (footprint "eagle-import:R0805")
      (libsource (lib "eagle-import") (part "R-EU_R0805"))
    )
    (comp (ref "R9")
      (value "86K6")
      (footprint "eagle-import:R0805")
      (libsource (lib "eagle-import") (part "R-EU_R0805"))
    )
    (comp (ref "R10")
      (value "10K")
      (footprint "eagle-import:R0805")
      (libsource (lib "eagle-import") (part "R-EU_R0805"))
    )
    (comp (ref "R11")
      (value "10K")
      (footprint "eagle-import:R0805")
      (libsource (lib "eagle-import") (part "R-EU_R0805"))
    )
    (comp (ref "R12")
      (value "10K")
      (footprint "eagle-import:R0805")
      (libsource (lib "eagle-import") (part "R-EU_R0805"))
    )
    (comp (ref "R13")
      (value "10K")
      (footprint "eagle-import:R0805")
      (libsource (lib "eagle-import") (part "R-EU_R0805"))
    )
    (comp (ref "RN1")
      (value "DR1206-33R-4/8")
      (footprint "eagle-import:CAY16")
      (libsource (lib "eagle-import") (part "R_ARRAY4"))
    )
    (comp (ref "SH1")
      (value "SHORTNOHOLE")
      (footprint "eagle-import:SHORT_NOHOLE")
      (libsource (lib "eagle-import") (part "SHORTNOHOLE"))
    )
    (comp (ref "TR1")
      (value "SRF0703-821M")
      (footprint "eagle-import:SRF0703")
      (libsource (lib "eagle-import") (part "BOURNS_SRF0703INV"))
    )
    (comp (ref "X1")
      (value "172648-0102")
      (footprint "eagle-import:MINIFIT_39301020")
      (libsource (lib "eagle-import") (part "MINIFIT_39301020"))
    )
    (comp (ref "X2")
      (value "77317-104-28LF")
      (footprint "eagle-import:77317-104-28LF")
      (libsource (lib "eagle-import") (part "77317-104-28LF"))
    )
    (comp (ref "ZD1")
      (value "SMAJ51A")
      (footprint "eagle-import:DO214AA")
      (libsource (lib "eagle-import") (part "P6SMB68A"))
    )
  )
  (nets
    (net (code "1") (name "+3V3") (class "Default")
      (node (ref "C18") (pin "2") (pinfunction "2_2") (pintype "passive"))
      (node (ref "C21") (pin "1") (pinfunction "1_1") (pintype "passive"))
      (node (ref "C25") (pin "1") (pinfunction "1_1") (pintype "passive"))
      (node (ref "C27") (pin "1") (pinfunction "1_1") (pintype "passive"))
      (node (ref "C28") (pin "2") (pinfunction "2_2") (pintype "passive"))
      (node (ref "C29") (pin "1") (pinfunction "1_1") (pintype "passive"))
      (node (ref "C36") (pin "2") (pinfunction "2_2") (pintype "passive"))
      (node (ref "C40") (pin "2") (pinfunction "2_2") (pintype "passive"))
      (node (ref "C47") (pin "1") (pinfunction "1_1") (pintype "passive"))
      (node (ref "C8") (pin "2") (pinfunction "2_2") (pintype "passive"))
      (node (ref "FB1") (pin "P$1") (pinfunction "1_P$1") (pintype "passive"))
      (node (ref "IC1") (pin "16") (pinfunction "VDD2_16") (pintype "passive"))
      (node (ref "IC12") (pin "4") (pinfunction "V+_4") (pintype "power_in"))
      (node (ref "IC3") (pin "10") (pinfunction "EN2_10") (pintype "input"))
      (node (ref "IC3") (pin "16") (pinfunction "VDD2_16") (pintype "passive"))
      (node (ref "IC5") (pin "5") (pinfunction "OUT_5") (pintype "passive"))
      (node (ref "IC6") (pin "5") (pinfunction "V+_5") (pintype "power_in"))
      (node (ref "IC7") (pin "6") (pinfunction "VCC_6") (pintype "passive"))
      (node (ref "IC8") (pin "17") (pinfunction "VDD_2_17") (pintype "passive"))
      (node (ref "IC8") (pin "48") (pinfunction "VDD_1_48") (pintype "bidirectional"))
      (node (ref "JP1") (pin "1") (pinfunction "1_1") (pintype "passive"))
      (node (ref "JP2") (pin "1") (pinfunction "1_1") (pintype "passive"))
      (node (ref "NTC1") (pin "1") (pinfunction "P$1_1") (pintype "bidirectional"))
      (node (ref "NTC2") (pin "1") (pinfunction "P$1_1") (pintype "bidirectional"))
      (node (ref "Q10") (pin "2") (pinfunction "S_2") (pintype "passive"))
      (node (ref "Q5") (pin "2") (pinfunction "S_2") (pintype "passive"))
      (node (ref "R20") (pin "1") (pinfunction "1_1") (pintype "passive"))
      (node (ref "R23") (pin "1") (pinfunction "1_1") (pintype "passive"))
    )
    (net (code "2") (name "+8V") (class "Default")
      (node (ref "C14") (pin "1") (pinfunction "1_1") (pintype "passive"))
      (node (ref "C22") (pin "2") (pinfunction "2_2") (pintype "passive"))
      (node (ref "C45") (pin "1") (pinfunction "1_1") (pintype "passive"))
      (node (ref "IC10") (pin "8") (pinfunction "V+_8") (pintype "power_in"))
      (node (ref "IC5") (pin "1") (pinfunction "IN_1") (pintype "input"))
      (node (ref "IC5") (pin "3") (pinfunction "ON/~{OFF}_3") (pintype "input"))
      (node (ref "R4") (pin "1") (pinfunction "1_1") (pintype "passive"))
    )
    (net (code "3") (name "+VAUX") (class "Default")
      (node (ref "X2") (pin "2") (pinfunction "1_2") (pintype "passive"))
    )
    (net (code "4") (name "+VREF") (class "Default")
      (node (ref "C39") (pin "2") (pinfunction "2_2") (pintype "passive"))
      (node (ref "IC8") (pin "25") (pinfunction "VREFSD+_25") (pintype "passive"))
      (node (ref "IC9") (pin "1") (pinfunction "C_1") (pintype "passive"))
      (node (ref "IC9") (pin "2") (pinfunction "R_2") (pintype "passive"))
      (node (ref "R23") (pin "2") (pinfunction "2_2") (pintype "passive"))
    )
    (net (code "5") (name "-8V") (class "Default")
      (node (ref "C5") (pin "1") (pinfunction "1_1") (pintype "passive"))
      (node (ref "C51") (pin "2") (pinfunction "2_2") (pintype "passive"))
      (node (ref "IC10") (pin "4") (pinfunction "V-_4") (pintype "power_in"))
      (node (ref "R2") (pin "1") (pinfunction "1_1") (pintype "passive"))
    )
    (net (code "6") (name "AGND") (class "Default")
      (node (ref "C39") (pin "1") (pinfunction "1_1") (pintype "passive"))
      (node (ref "IC8") (pin "23") (pinfunction "VSSSD/VREFSD-_23") (pintype "passive"))
      (node (ref "IC8") (pin "8") (pinfunction "VSSA/VREF-_8") (pintype "passive"))
      (node (ref "SH2") (pin "1") (pinfunction "GND_A_1") (pintype "bidirectional"))
    )
    (net (code "7") (name "BOOT0") (class "Default")
      (node (ref "IC3") (pin "13") (pinfunction "B2_13") (pintype "output"))
      (node (ref "IC8") (pin "44") (pinfunction "BOOT0_44") (pintype "input"))
      (node (ref "JP1") (pin "2") (pinfunction "2_2") (pintype "passive"))
      (node (ref "R15") (pin "2") (pinfunction "2_2") (pintype "passive"))
    )
    (net (code "8") (name "CC#1") (class "Default")
      (node (ref "IC12") (pin "7") (pinfunction "OUT_7") (pintype "output"))
      (node (ref "IC8") (pin "3") (pinfunction "PC14-OSC32_IN_3") (pintype "bidirectional"))
    )
    (net (code "9") (name "CC#2") (class "Default")
      (node (ref "IC12") (pin "1") (pinfunction "OUT_1") (pintype "output"))
      (node (ref "IC8") (pin "4") (pinfunction "PC15-OSC32_OUT_4") (pintype "bidirectional"))
    )
    (net (code "10") (name "CC_LED#1") (class "Default")
      (node (ref "IC8") (pin "2") (pinfunction "PC13_2") (pintype "bidirectional"))
      (node (ref "Q5") (pin "1") (pinfunction "G_1") (pintype "passive"))
      (node (ref "R51") (pin "2") (pinfunction "2_2") (pintype "passive"))
    )
    (net (code "11") (name "CC_LED#2") (class "Default")
      (node (ref "IC8") (pin "11") (pinfunction "PA1_11") (pintype "bidirectional"))
      (node (ref "Q10") (pin "1") (pinfunction "G_1") (pintype "passive"))
      (node (ref "R77") (pin "2") (pinfunction "2_2") (pintype "passive"))
    )
    (net (code "12") (name "DC_OUT+") (class "Default")
      (node (ref "C3") (pin "2") (pinfunction "2_2") (pintype "passive"))
      (node (ref "C46") (pin "+") (pinfunction "+_+") (pintype "passive"))
      (node (ref "C50") (pin "1") (pinfunction "1_1") (pintype "passive"))
      (node (ref "C52") (pin "1") (pinfunction "1_1") (pintype "passive"))
      (node (ref "C6") (pin "1") (pinfunction "1_1") (pintype "passive"))
      (node (ref "C68") (pin "+") (pinfunction "+_+") (pintype "passive"))
      (node (ref "C71") (pin "1") (pinfunction "1_1") (pintype "passive"))
      (node (ref "C72") (pin "1") (pinfunction "1_1") (pintype "passive"))
      (node (ref "C9") (pin "1") (pinfunction "1_1") (pintype "passive"))
      (node (ref "IC11") (pin "6") (pinfunction "IVINN_6") (pintype "input"))
      (node (ref "IC11") (pin "7") (pinfunction "IVINP_7") (pintype "input"))
      (node (ref "IC13") (pin "6") (pinfunction "IVINN_6") (pintype "input"))
      (node (ref "IC13") (pin "7") (pinfunction "IVINP_7") (pintype "input"))
      (node (ref "IC2") (pin "2") (pinfunction "VIN_2") (pintype "power_in"))
      (node (ref "L1") (pin "4") (pinfunction "2_4") (pintype "passive"))
      (node (ref "Q2") (pin "2") (pinfunction "D_2") (pintype "passive"))
      (node (ref "Q7") (pin "2") (pinfunction "D_2") (pintype "passive"))
      (node (ref "R28") (pin "1") (pinfunction "1_1") (pintype "passive"))
      (node (ref "R29") (pin "1") (pinfunction "1_1") (pintype "passive"))
      (node (ref "R3") (pin "2") (pinfunction "2_2") (pintype "passive"))
      (node (ref "R54") (pin "1") (pinfunction "1_1") (pintype "passive"))
      (node (ref "R55") (pin "1") (pinfunction "1_1") (pintype "passive"))
      (node (ref "ZD1") (pin "C") (pinfunction "C_C") (pintype "passive"))
    )
    (net (code "13") (name "DC_OUT-") (class "Default")
      (node (ref "C2") (pin "1") (pinfunction "1_1") (pintype "passive"))
      (node (ref "C46") (pin "-") (pinfunction "-_-") (pintype "passive"))
      (node (ref "C50") (pin "2") (pinfunction "2_2") (pintype "passive"))
      (node (ref "C52") (pin "2") (pinfunction "2_2") (pintype "passive"))
      (node (ref "C57") (pin "2") (pinfunction "2_2") (pintype "passive"))
      (node (ref "C59") (pin "2") (pinfunction "2_2") (pintype "passive"))
      (node (ref "C60") (pin "2") (pinfunction "2_2") (pintype "passive"))
      (node (ref "C61") (pin "2") (pinfunction "-_2") (pintype "passive"))
      (node (ref "C62") (pin "-") (pinfunction "-_-") (pintype "passive"))
      (node (ref "C63") (pin "2") (pinfunction "2_2") (pintype "passive"))
      (node (ref "C68") (pin "-") (pinfunction "-_-") (pintype "passive"))
      (node (ref "C71") (pin "2") (pinfunction "2_2") (pintype "passive"))
      (node (ref "C72") (pin "2") (pinfunction "2_2") (pintype "passive"))
      (node (ref "C77") (pin "2") (pinfunction "2_2") (pintype "passive"))
      (node (ref "C79") (pin "2") (pinfunction "2_2") (pintype "passive"))
      (node (ref "C80") (pin "2") (pinfunction "2_2") (pintype "passive"))
      (node (ref "C81") (pin "2") (pinfunction "-_2") (pintype "passive"))
      (node (ref "C82") (pin "-") (pinfunction "-_-") (pintype "passive"))
      (node (ref "C83") (pin "2") (pinfunction "2_2") (pintype "passive"))
      (node (ref "CH1") (pin "GND") (pinfunction "GND_GND") (pintype "bidirectional"))
      (node (ref "CH2") (pin "GND") (pinfunction "GND_GND") (pintype "bidirectional"))
      (node (ref "D5") (pin "A") (pinfunction "A_A") (pintype "passive"))
      (node (ref "D8") (pin "A") (pinfunction "A_A") (pintype "passive"))
      (node (ref "J3") (pin "1") (pinfunction "1_1") (pintype "passive"))
      (node (ref "J3") (pin "1.1") (pinfunction "1_1.1") (pintype "passive"))
      (node (ref "J5") (pin "1") (pinfunction "1_1") (pintype "passive"))
      (node (ref "J5") (pin "1.1") (pinfunction "1_1.1") (pintype "passive"))
      (node (ref "L1") (pin "2") (pinfunction "2_2") (pintype "passive"))
      (node (ref "LED1") (pin "CC") (pinfunction "C_CC") (pintype "passive"))
      (node (ref "LED2") (pin "CC") (pinfunction "C_CC") (pintype "passive"))
      (node (ref "Q3") (pin "3") (pinfunction "S_3") (pintype "passive"))
      (node (ref "Q8") (pin "3") (pinfunction "S_3") (pintype "passive"))
      (node (ref "R39") (pin "1") (pinfunction "1_1") (pintype "passive"))
      (node (ref "R43") (pin "2") (pinfunction "2_2") (pintype "passive"))
      (node (ref "R65") (pin "1") (pinfunction "1_1") (pintype "passive"))
      (node (ref "R69") (pin "2") (pinfunction "2_2") (pintype "passive"))
      (node (ref "SH1") (pin "2") (pinfunction "GND_B_2") (pintype "bidirectional"))
      (node (ref "SH3") (pin "1") (pinfunction "GND_A_1") (pintype "bidirectional"))
      (node (ref "SH4") (pin "1") (pinfunction "GND_A_1") (pintype "bidirectional"))
      (node (ref "X4") (pin "1") (pinfunction "1_1") (pintype "passive"))
      (node (ref "X4") (pin "10") (pinfunction "1_10") (pintype "passive"))
      (node (ref "X4") (pin "2") (pinfunction "1_2") (pintype "passive"))
      (node (ref "X4") (pin "3") (pinfunction "1_3") (pintype "passive"))
      (node (ref "X4") (pin "4") (pinfunction "1_4") (pintype "passive"))
      (node (ref "X4") (pin "5") (pinfunction "1_5") (pintype "passive"))
      (node (ref "X4") (pin "6") (pinfunction "1_6") (pintype "passive"))
      (node (ref "X4") (pin "7") (pinfunction "1_7") (pintype "passive"))
      (node (ref "X4") (pin "8") (pinfunction "1_8") (pintype "passive"))
      (node (ref "X4") (pin "9") (pinfunction "1_9") (pintype "passive"))
      (node (ref "ZD1") (pin "A") (pinfunction "A_A") (pintype "passive"))
      (node (ref "ZD3") (pin "A") (pinfunction "A_A") (pintype "passive"))
      (node (ref "ZD5") (pin "A") (pinfunction "A_A") (pintype "passive"))
    )
    (net (code "14") (name "DIB_5V") (class "Default")
      (node (ref "X2") (pin "23") (pinfunction "1_23") (pintype "passive"))
      (node (ref "X2") (pin "24") (pinfunction "1_24") (pintype "passive"))
    )
    (net (code "15") (name "DIB_12V") (class "Default")
      (node (ref "X2") (pin "21") (pinfunction "1_21") (pintype "passive"))
      (node (ref "X2") (pin "22") (pinfunction "1_22") (pintype "passive"))
    )
    (net (code "16") (name "DIB_A0") (class "Default")
      (node (ref "IC4") (pin "1") (pinfunction "A0_1") (pintype "input"))
      (node (ref "R13") (pin "2") (pinfunction "2_2") (pintype "passive"))
      (node (ref "X2") (pin "17") (pinfunction "1_17") (pintype "passive"))
    )
    (net (code "17") (name "DIB_A1") (class "Default")
      (node (ref "IC4") (pin "2") (pinfunction "A1_2") (pintype "input"))
      (node (ref "R12") (pin "2") (pinfunction "2_2") (pintype "passive"))
      (node (ref "X2") (pin "19") (pinfunction "1_19") (pintype "passive"))
    )
    (net (code "18") (name "DIB_A2") (class "Default")
      (node (ref "IC4") (pin "3") (pinfunction "A2_3") (pintype "input"))
      (node (ref "R11") (pin "2") (pinfunction "2_2") (pintype "passive"))
      (node (ref "X2") (pin "18") (pinfunction "1_18") (pintype "passive"))
    )
    (net (code "19") (name "DIB_BOOT0") (class "Default")
      (node (ref "IC3") (pin "4") (pinfunction "A2_4") (pintype "input"))
      (node (ref "X2") (pin "26") (pinfunction "1_26") (pintype "passive"))
    )
    (net (code "20") (name "DIB_CSA") (class "Default")
      (node (ref "IC1") (pin "5") (pinfunction "A4_5") (pintype "input"))
      (node (ref "X2") (pin "9") (pinfunction "1_9") (pintype "passive"))
    )
    (net (code "21") (name "DIB_CSB") (class "Default")
      (node (ref "X2") (pin "12") (pinfunction "1_12") (pintype "passive"))
    )
    (net (code "22") (name "DIB_IRQ") (class "Default")
      (node (ref "IC1") (pin "7") (pinfunction "A6_7") (pintype "output"))
      (node (ref "X2") (pin "10") (pinfunction "1_10") (pintype "passive"))
    )
    (net (code "23") (name "DIB_MISO") (class "Default")
      (node (ref "IC1") (pin "6") (pinfunction "A5_6") (pintype "output"))
      (node (ref "X2") (pin "14") (pinfunction "1_14") (pintype "passive"))
    )
    (net (code "24") (name "DIB_MOSI") (class "Default")
      (node (ref "IC3") (pin "3") (pinfunction "A1_3") (pintype "input"))
      (node (ref "X2") (pin "15") (pinfunction "1_15") (pintype "passive"))
    )
    (net (code "25") (name "DIB_NFAULT") (class "Default")
      (node (ref "X2") (pin "3") (pinfunction "1_3") (pintype "passive"))
    )
    (net (code "26") (name "DIB_NRESET") (class "Default")
      (node (ref "IC1") (pin "2") (pinfunction "A1_2") (pintype "input"))
      (node (ref "X2") (pin "4") (pinfunction "1_4") (pintype "passive"))
    )
    (net (code "27") (name "DIB_SCL") (class "Default")
      (node (ref "IC4") (pin "6") (pinfunction "SCL_6") (pintype "bidirectional"))
      (node (ref "X2") (pin "5") (pinfunction "1_5") (pintype "passive"))
    )
    (net (code "28") (name "DIB_SCLK") (class "Default")
      (node (ref "IC1") (pin "4") (pinfunction "A3_4") (pintype "input"))
      (node (ref "X2") (pin "13") (pinfunction "1_13") (pintype "passive"))
    )
    (net (code "29") (name "DIB_SDA") (class "Default")
      (node (ref "IC4") (pin "5") (pinfunction "SDA_5") (pintype "bidirectional"))
      (node (ref "X2") (pin "8") (pinfunction "1_8") (pintype "passive"))
    )
    (net (code "30") (name "DIB_SYNC") (class "Default")
      (node (ref "IC1") (pin "3") (pinfunction "A2_3") (pintype "input"))
      (node (ref "X2") (pin "6") (pinfunction "1_6") (pintype "passive"))
    )
    (net (code "31") (name "DIB_UART_RX") (class "Default")
      (node (ref "IC3") (pin "6") (pinfunction "A4_6") (pintype "output"))
      (node (ref "X2") (pin "28") (pinfunction "1_28") (pintype "passive"))
    )
    (net (code "32") (name "DIB_UART_TX") (class "Default")
      (node (ref "IC3") (pin "5") (pinfunction "A3_5") (pintype "input"))
      (node (ref "X2") (pin "27") (pinfunction "1_27") (pintype "passive"))
    )
    (net (code "33") (name "FB1") (class "Default")
      (node (ref "IC11") (pin "11") (pinfunction "FB_11") (pintype "input"))
      (node (ref "IC12") (pin "10") (pinfunction "+IN_10") (pintype "input"))
      (node (ref "R41") (pin "1") (pinfunction "1_1") (pintype "passive"))
      (node (ref "R48") (pin "2") (pinfunction "2_2") (pintype "passive"))
      (node (ref "R50") (pin "2") (pinfunction "2_2") (pintype "passive"))
    )
    (net (code "34") (name "FB2") (class "Default")
      (node (ref "IC12") (pin "12") (pinfunction "+IN_12") (pintype "input"))
      (node (ref "IC13") (pin "11") (pinfunction "FB_11") (pintype "input"))
      (node (ref "R67") (pin "1") (pinfunction "1_1") (pintype "passive"))
      (node (ref "R74") (pin "2") (pinfunction "2_2") (pintype "passive"))
      (node (ref "R76") (pin "2") (pinfunction "2_2") (pintype "passive"))
    )
    (net (code "35") (name "GND") (class "Default")
      (node (ref "C12") (pin "2") (pinfunction "2_2") (pintype "passive"))
      (node (ref "C13") (pin "2") (pinfunction "2_2") (pintype "passive"))
      (node (ref "C14") (pin "2") (pinfunction "2_2") (pintype "passive"))
      (node (ref "C15") (pin "2") (pinfunction "2_2") (pintype "passive"))
      (node (ref "C16") (pin "1") (pinfunction "1_1") (pintype "passive"))
      (node (ref "C18") (pin "1") (pinfunction "1_1") (pintype "passive"))
      (node (ref "C19") (pin "1") (pinfunction "1_1") (pintype "passive"))
      (node (ref "C21") (pin "2") (pinfunction "2_2") (pintype "passive"))
      (node (ref "C22") (pin "1") (pinfunction "1_1") (pintype "passive"))
      (node (ref "C23") (pin "1") (pinfunction "1_1") (pintype "passive"))
      (node (ref "C25") (pin "2") (pinfunction "2_2") (pintype "passive"))
      (node (ref "C26") (pin "2") (pinfunction "2_2") (pintype "passive"))
      (node (ref "C27") (pin "2") (pinfunction "2_2") (pintype "passive"))
      (node (ref "C28") (pin "1") (pinfunction "1_1") (pintype "passive"))
      (node (ref "C29") (pin "2") (pinfunction "2_2") (pintype "passive"))
      (node (ref "C31") (pin "2") (pinfunction "2_2") (pintype "passive"))
      (node (ref "C32") (pin "1") (pinfunction "1_1") (pintype "passive"))
      (node (ref "C33") (pin "1") (pinfunction "1_1") (pintype "passive"))
      (node (ref "C34") (pin "1") (pinfunction "1_1") (pintype "passive"))
      (node (ref "C35") (pin "1") (pinfunction "1_1") (pintype "passive"))
      (node (ref "C37") (pin "1") (pinfunction "1_1") (pintype "passive"))
      (node (ref "C38") (pin "1") (pinfunction "1_1") (pintype "passive"))
      (node (ref "C4") (pin "2") (pinfunction "2_2") (pintype "passive"))
      (node (ref "C40") (pin "1") (pinfunction "1_1") (pintype "passive"))
      (node (ref "C41") (pin "1") (pinfunction "1_1") (pintype "passive"))
      (node (ref "C42") (pin "1") (pinfunction "1_1") (pintype "passive"))
      (node (ref "C43") (pin "1") (pinfunction "1_1") (pintype "passive"))
      (node (ref "C44") (pin "1") (pinfunction "1_1") (pintype "passive"))
      (node (ref "C45") (pin "2") (pinfunction "2_2") (pintype "passive"))
      (node (ref "C47") (pin "2") (pinfunction "2_2") (pintype "passive"))
      (node (ref "C49") (pin "2") (pinfunction "2_2") (pintype "passive"))
      (node (ref "C5") (pin "2") (pinfunction "2_2") (pintype "passive"))
      (node (ref "C51") (pin "1") (pinfunction "1_1") (pintype "passive"))
      (node (ref "C53") (pin "2") (pinfunction "2_2") (pintype "passive"))
      (node (ref "C55") (pin "2") (pinfunction "2_2") (pintype "passive"))
      (node (ref "C6") (pin "2") (pinfunction "2_2") (pintype "passive"))
      (node (ref "C64") (pin "1") (pinfunction "1_1") (pintype "passive"))
      (node (ref "C66") (pin "1") (pinfunction "1_1") (pintype "passive"))
      (node (ref "C70") (pin "2") (pinfunction "2_2") (pintype "passive"))
      (node (ref "C73") (pin "2") (pinfunction "2_2") (pintype "passive"))
      (node (ref "C75") (pin "2") (pinfunction "2_2") (pintype "passive"))
      (node (ref "C8") (pin "1") (pinfunction "1_1") (pintype "passive"))
      (node (ref "C84") (pin "1") (pinfunction "1_1") (pintype "passive"))
      (node (ref "C86") (pin "1") (pinfunction "1_1") (pintype "passive"))
      (node (ref "C9") (pin "2") (pinfunction "2_2") (pintype "passive"))
      (node (ref "D2") (pin "A") (pinfunction "A_A") (pintype "passive"))
      (node (ref "GND") (pin "1") (pinfunction "P$1_1") (pintype "bidirectional"))
      (node (ref "IC1") (pin "9") (pinfunction "GND2_9") (pintype "passive"))
      (node (ref "IC11") (pin "12") (pinfunction "GND_12") (pintype "passive"))
      (node (ref "IC11") (pin "21") (pinfunction "SYNC_21") (pintype "input"))
      (node (ref "IC11") (pin "23") (pinfunction "GND_23") (pintype "passive"))
      (node (ref "IC11") (pin "28") (pinfunction "GND_28") (pintype "passive"))
      (node (ref "IC11") (pin "TP") (pinfunction "GND_PAD_TP") (pintype "passive"))
      (node (ref "IC12") (pin "11") (pinfunction "V-_11") (pintype "power_in"))
      (node (ref "IC13") (pin "12") (pinfunction "GND_12") (pintype "passive"))
      (node (ref "IC13") (pin "21") (pinfunction "SYNC_21") (pintype "input"))
      (node (ref "IC13") (pin "23") (pinfunction "GND_23") (pintype "passive"))
      (node (ref "IC13") (pin "28") (pinfunction "GND_28") (pintype "passive"))
      (node (ref "IC13") (pin "TP") (pinfunction "GND_PAD_TP") (pintype "passive"))
      (node (ref "IC2") (pin "9") (pinfunction "GND_9") (pintype "passive"))
      (node (ref "IC2") (pin "TP") (pinfunction "TP_TP") (pintype "passive"))
      (node (ref "IC3") (pin "15") (pinfunction "GND2_15") (pintype "passive"))
      (node (ref "IC3") (pin "9") (pinfunction "GND2_2_9") (pintype "passive"))
      (node (ref "IC5") (pin "2") (pinfunction "GND_2") (pintype "passive"))
      (node (ref "IC6") (pin "2") (pinfunction "V-_2") (pintype "power_in"))
      (node (ref "IC7") (pin "3") (pinfunction "GND_3") (pintype "power_in"))
      (node (ref "IC8") (pin "47") (pinfunction "VSS_1_47") (pintype "bidirectional"))
      (node (ref "IC9") (pin "3") (pinfunction "A_3") (pintype "passive"))
      (node (ref "R10") (pin "1") (pinfunction "1_1") (pintype "passive"))
      (node (ref "R15") (pin "1") (pinfunction "1_1") (pintype "passive"))
      (node (ref "R19") (pin "1") (pinfunction "1_1") (pintype "passive"))
      (node (ref "R21") (pin "2") (pinfunction "2_2") (pintype "passive"))
      (node (ref "R22") (pin "2") (pinfunction "2_2") (pintype "passive"))
      (node (ref "R30") (pin "1") (pinfunction "1_1") (pintype "passive"))
      (node (ref "R34") (pin "1") (pinfunction "1_1") (pintype "passive"))
      (node (ref "R44") (pin "1") (pinfunction "1_1") (pintype "passive"))
      (node (ref "R47") (pin "1") (pinfunction "1_1") (pintype "passive"))
      (node (ref "R48") (pin "1") (pinfunction "1_1") (pintype "passive"))
      (node (ref "R49") (pin "1") (pinfunction "1_1") (pintype "passive"))
      (node (ref "R5") (pin "1") (pinfunction "1_1") (pintype "passive"))
      (node (ref "R53") (pin "1") (pinfunction "1_1") (pintype "passive"))
      (node (ref "R56") (pin "1") (pinfunction "1_1") (pintype "passive"))
      (node (ref "R6") (pin "1") (pinfunction "1_1") (pintype "passive"))
      (node (ref "R60") (pin "1") (pinfunction "1_1") (pintype "passive"))
      (node (ref "R70") (pin "1") (pinfunction "1_1") (pintype "passive"))
      (node (ref "R73") (pin "1") (pinfunction "1_1") (pintype "passive"))
      (node (ref "R74") (pin "1") (pinfunction "1_1") (pintype "passive"))
      (node (ref "R75") (pin "1") (pinfunction "1_1") (pintype "passive"))
      (node (ref "R79") (pin "1") (pinfunction "1_1") (pintype "passive"))
      (node (ref "R8") (pin "1") (pinfunction "1_1") (pintype "passive"))
      (node (ref "SH1") (pin "1") (pinfunction "GND_A_1") (pintype "bidirectional"))
      (node (ref "SH2") (pin "2") (pinfunction "GND_B_2") (pintype "bidirectional"))
      (node (ref "SH3") (pin "2") (pinfunction "GND_B_2") (pintype "bidirectional"))
      (node (ref "SH4") (pin "2") (pinfunction "GND_B_2") (pintype "bidirectional"))
      (node (ref "TR1") (pin "4") (pinfunction "4_4") (pintype "passive"))
      (node (ref "X3") (pin "3") (pinfunction "S_3") (pintype "passive"))
    )
    (net (code "36") (name "GNDIO") (class "Default")
      (node (ref "C17") (pin "2") (pinfunction "2_2") (pintype "passive"))
      (node (ref "C20") (pin "1") (pinfunction "1_1") (pintype "passive"))
      (node (ref "C7") (pin "2") (pinfunction "2_2") (pintype "passive"))
      (node (ref "IC1") (pin "8") (pinfunction "GND1_8") (pintype "passive"))
      (node (ref "IC3") (pin "2") (pinfunction "GND1_2_2") (pintype "passive"))
      (node (ref "IC3") (pin "8") (pinfunction "GND1_8") (pintype "passive"))
      (node (ref "IC4") (pin "4") (pinfunction "GND_4") (pintype "passive"))
      (node (ref "IC4") (pin "7") (pinfunction "WP_7") (pintype "input"))
      (node (ref "X2") (pin "11") (pinfunction "1_11") (pintype "passive"))
      (node (ref "X2") (pin "16") (pinfunction "1_16") (pintype "passive"))
      (node (ref "X2") (pin "20") (pinfunction "1_20") (pintype "passive"))
      (node (ref "X2") (pin "25") (pinfunction "1_25") (pintype "passive"))
      (node (ref "X2") (pin "7") (pinfunction "1_7") (pintype "passive"))
    )
    (net (code "37") (name "INTVCC1") (class "Default")
      (node (ref "C55") (pin "1") (pinfunction "1_1") (pintype "passive"))
      (node (ref "D4") (pin "3") (pinfunction "CA_3") (pintype "passive"))
      (node (ref "IC11") (pin "2") (pinfunction "INTVCC_2") (pintype "passive"))
      (node (ref "R45") (pin "1") (pinfunction "1_1") (pintype "passive"))
      (node (ref "R46") (pin "2") (pinfunction "2_2") (pintype "passive"))
    )
    (net (code "38") (name "INTVCC2") (class "Default")
      (node (ref "C75") (pin "1") (pinfunction "1_1") (pintype "passive"))
      (node (ref "D7") (pin "3") (pinfunction "CA_3") (pintype "passive"))
      (node (ref "IC13") (pin "2") (pinfunction "INTVCC_2") (pintype "passive"))
      (node (ref "R71") (pin "1") (pinfunction "1_1") (pintype "passive"))
      (node (ref "R72") (pin "2") (pinfunction "2_2") (pintype "passive"))
    )
    (net (code "39") (name "IRQ") (class "Default")
      (node (ref "IC1") (pin "10") (pinfunction "B6_10") (pintype "input"))
      (node (ref "IC8") (pin "33") (pinfunction "PA12_33") (pintype "bidirectional"))
    )
    (net (code "40") (name "I_MON#1") (class "Default")
      (node (ref "C42") (pin "2") (pinfunction "2_2") (pintype "passive"))
      (node (ref "IC8") (pin "19") (pinfunction "PB1_19") (pintype "bidirectional"))
      (node (ref "R25") (pin "1") (pinfunction "1_1") (pintype "passive"))
    )
    (net (code "41") (name "I_MON#2") (class "Default")
      (node (ref "C44") (pin "2") (pinfunction "2_2") (pintype "passive"))
      (node (ref "IC8") (pin "21") (pinfunction "PE8_21") (pintype "bidirectional"))
      (node (ref "R27") (pin "1") (pinfunction "1_1") (pintype "passive"))
    )
    (net (code "42") (name "I_MON1") (class "Default")
      (node (ref "C64") (pin "2") (pinfunction "2_2") (pintype "passive"))
      (node (ref "R25") (pin "2") (pinfunction "2_2") (pintype "passive"))
      (node (ref "R40") (pin "1") (pinfunction "1_1") (pintype "passive"))
    )
    (net (code "43") (name "I_MON2") (class "Default")
      (node (ref "C84") (pin "2") (pinfunction "2_2") (pintype "passive"))
      (node (ref "R27") (pin "2") (pinfunction "2_2") (pintype "passive"))
      (node (ref "R66") (pin "1") (pinfunction "1_1") (pintype "passive"))
    )
    (net (code "44") (name "I_SET#1") (class "Default")
      (node (ref "I_SET1") (pin "1") (pinfunction "1_1") (pintype "passive"))
      (node (ref "R33") (pin "1") (pinfunction "1_1") (pintype "passive"))
    )
    (net (code "45") (name "I_SET#2") (class "Default")
      (node (ref "I_SET2") (pin "1") (pinfunction "1_1") (pintype "passive"))
      (node (ref "R59") (pin "1") (pinfunction "1_1") (pintype "passive"))
    )
    (net (code "46") (name "I_SET_OUT#1") (class "Default")
      (node (ref "IC6") (pin "1") (pinfunction "I_1") (pintype "input"))
      (node (ref "IC8") (pin "45") (pinfunction "PB8_45") (pintype "bidirectional"))
      (node (ref "R14") (pin "2") (pinfunction "2_2") (pintype "passive"))
    )
    (net (code "47") (name "I_SET_OUT#2") (class "Default")
      (node (ref "IC6") (pin "3") (pinfunction "I_3") (pintype "input"))
      (node (ref "IC8") (pin "46") (pinfunction "PB9_46") (pintype "bidirectional"))
      (node (ref "R17") (pin "2") (pinfunction "2_2") (pintype "passive"))
    )
    (net (code "48") (name "MISO") (class "Default")
      (node (ref "IC1") (pin "11") (pinfunction "B5_11") (pintype "input"))
      (node (ref "IC8") (pin "30") (pinfunction "PA9_30") (pintype "bidirectional"))
    )
    (net (code "49") (name "MOSI") (class "Default")
      (node (ref "IC8") (pin "31") (pinfunction "PA10_31") (pintype "bidirectional"))
      (node (ref "RN1") (pin "5") (pinfunction "2_5") (pintype "passive"))
    )
    (net (code "50") (name "NRST") (class "Default")
      (node (ref "C36") (pin "1") (pinfunction "1_1") (pintype "passive"))
      (node (ref "IC8") (pin "7") (pinfunction "NRST_7") (pintype "input"))
      (node (ref "JP3") (pin "2") (pinfunction "2_2") (pintype "passive"))
      (node (ref "R20") (pin "2") (pinfunction "2_2") (pintype "passive"))
      (node (ref "RN2") (pin "3") (pinfunction "1_3") (pintype "passive"))
    )
    (net (code "51") (name "NSS") (class "Default")
      (node (ref "IC8") (pin "32") (pinfunction "PA11_32") (pintype "bidirectional"))
      (node (ref "RN1") (pin "6") (pinfunction "2_6") (pintype "passive"))
    )
    (net (code "52") (name "Net-(C4-Pad1)") (class "Default")
      (node (ref "C4") (pin "1") (pinfunction "1_1") (pintype "passive"))
      (node (ref "D1") (pin "A") (pinfunction "A_A") (pintype "passive"))
      (node (ref "R2") (pin "2") (pinfunction "2_2") (pintype "passive"))
    )
    (net (code "53") (name "Net-(C11-Pad2)") (class "Default")
      (node (ref "C11") (pin "2") (pinfunction "2_2") (pintype "passive"))
      (node (ref "R5") (pin "2") (pinfunction "2_2") (pintype "passive"))
    )
    (net (code "54") (name "Net-(C12-Pad1)") (class "Default")
      (node (ref "C12") (pin "1") (pinfunction "1_1") (pintype "passive"))
      (node (ref "C13") (pin "1") (pinfunction "1_1") (pintype "passive"))
      (node (ref "R4") (pin "2") (pinfunction "2_2") (pintype "passive"))
      (node (ref "R7") (pin "2") (pinfunction "2_2") (pintype "passive"))
      (node (ref "TR1") (pin "3") (pinfunction "3_3") (pintype "passive"))
    )
    (net (code "55") (name "Net-(C19-Pad2)") (class "Default")
      (node (ref "C19") (pin "2") (pinfunction "2_2") (pintype "passive"))
      (node (ref "R9") (pin "1") (pinfunction "1_1") (pintype "passive"))
    )
    (net (code "56") (name "Net-(C24-Pad1)") (class "Default")
      (node (ref "C24") (pin "1") (pinfunction "1_1") (pintype "passive"))
      (node (ref "C26") (pin "1") (pinfunction "1_1") (pintype "passive"))
      (node (ref "I_SET1") (pin "2") (pinfunction "2_2") (pintype "passive"))
      (node (ref "R14") (pin "1") (pinfunction "1_1") (pintype "passive"))
    )
    (net (code "57") (name "Net-(C24-Pad2)") (class "Default")
      (node (ref "C24") (pin "2") (pinfunction "2_2") (pintype "passive"))
      (node (ref "R16") (pin "1") (pinfunction "1_1") (pintype "passive"))
    )
    (net (code "58") (name "Net-(C30-Pad1)") (class "Default")
      (node (ref "C30") (pin "1") (pinfunction "1_1") (pintype "passive"))
      (node (ref "C31") (pin "1") (pinfunction "1_1") (pintype "passive"))
      (node (ref "I_SET2") (pin "2") (pinfunction "2_2") (pintype "passive"))
      (node (ref "R17") (pin "1") (pinfunction "1_1") (pintype "passive"))
    )
    (net (code "59") (name "Net-(C30-Pad2)") (class "Default")
      (node (ref "C30") (pin "2") (pinfunction "2_2") (pintype "passive"))
      (node (ref "R18") (pin "1") (pinfunction "1_1") (pintype "passive"))
    )
    (net (code "60") (name "Net-(C58-Pad2)") (class "Default")
      (node (ref "C58") (pin "2") (pinfunction "2_2") (pintype "passive"))
      (node (ref "R39") (pin "2") (pinfunction "2_2") (pintype "passive"))
    )
    (net (code "61") (name "Net-(C67-Pad1)") (class "Default")
      (node (ref "C67") (pin "1") (pinfunction "1_1") (pintype "passive"))
      (node (ref "R47") (pin "2") (pinfunction "2_2") (pintype "passive"))
    )
    (net (code "62") (name "Net-(C78-Pad2)") (class "Default")
      (node (ref "C78") (pin "2") (pinfunction "2_2") (pintype "passive"))
      (node (ref "R65") (pin "2") (pinfunction "2_2") (pintype "passive"))
    )
    (net (code "63") (name "Net-(C87-Pad1)") (class "Default")
      (node (ref "C87") (pin "1") (pinfunction "1_1") (pintype "passive"))
      (node (ref "R73") (pin "2") (pinfunction "2_2") (pintype "passive"))
    )
    (net (code "64") (name "Net-(D1-PadC)") (class "Default")
      (node (ref "D1") (pin "C") (pinfunction "C_C") (pintype "passive"))
      (node (ref "TR1") (pin "2") (pinfunction "2_2") (pintype "passive"))
    )
    (net (code "65") (name "Net-(D3-CA)") (class "Default")
      (node (ref "D3") (pin "3") (pinfunction "CA_3") (pintype "passive"))
      (node (ref "Q1") (pin "3") (pinfunction "S_3") (pintype "passive"))
    )
    (net (code "66") (name "Net-(D3-K1)") (class "Default")
      (node (ref "D3") (pin "1") (pinfunction "K1_1") (pintype "passive"))
      (node (ref "Q1") (pin "1") (pinfunction "G_1") (pintype "passive"))
      (node (ref "R29") (pin "2") (pinfunction "2_2") (pintype "passive"))
      (node (ref "ZD2") (pin "C") (pinfunction "C_C") (pintype "passive"))
    )
    (net (code "67") (name "Net-(D3-K2)") (class "Default")
      (node (ref "C49") (pin "1") (pinfunction "1_1") (pintype "passive"))
      (node (ref "D3") (pin "2") (pinfunction "K2_2") (pintype "passive"))
      (node (ref "IC11") (pin "3") (pinfunction "VIN_3") (pintype "passive"))
    )
    (net (code "68") (name "Net-(D4-K1)") (class "Default")
      (node (ref "C54") (pin "1") (pinfunction "1_1") (pintype "passive"))
      (node (ref "D4") (pin "1") (pinfunction "K1_1") (pintype "passive"))
      (node (ref "D4") (pin "2") (pinfunction "K2_2") (pintype "passive"))
      (node (ref "IC11") (pin "27") (pinfunction "BOOST_27") (pintype "passive"))
    )
    (net (code "69") (name "Net-(D6-CA)") (class "Default")
      (node (ref "D6") (pin "3") (pinfunction "CA_3") (pintype "passive"))
      (node (ref "Q6") (pin "3") (pinfunction "S_3") (pintype "passive"))
    )
    (net (code "70") (name "Net-(D6-K1)") (class "Default")
      (node (ref "D6") (pin "1") (pinfunction "K1_1") (pintype "passive"))
      (node (ref "Q6") (pin "1") (pinfunction "G_1") (pintype "passive"))
      (node (ref "R55") (pin "2") (pinfunction "2_2") (pintype "passive"))
      (node (ref "ZD4") (pin "C") (pinfunction "C_C") (pintype "passive"))
    )
    (net (code "71") (name "Net-(D6-K2)") (class "Default")
      (node (ref "C70") (pin "1") (pinfunction "1_1") (pintype "passive"))
      (node (ref "D6") (pin "2") (pinfunction "K2_2") (pintype "passive"))
      (node (ref "IC13") (pin "3") (pinfunction "VIN_3") (pintype "passive"))
    )
    (net (code "72") (name "Net-(D7-K1)") (class "Default")
      (node (ref "C74") (pin "1") (pinfunction "1_1") (pintype "passive"))
      (node (ref "D7") (pin "1") (pinfunction "K1_1") (pintype "passive"))
      (node (ref "D7") (pin "2") (pinfunction "K2_2") (pintype "passive"))
      (node (ref "IC13") (pin "27") (pinfunction "BOOST_27") (pintype "passive"))
    )
    (net (code "73") (name "Net-(IC1-B2)") (class "Default")
      (node (ref "IC1") (pin "14") (pinfunction "B2_14") (pintype "output"))
      (node (ref "RN1") (pin "1") (pinfunction "1_1") (pintype "passive"))
    )
    (net (code "74") (name "Net-(IC1-B3)") (class "Default")
      (node (ref "IC1") (pin "13") (pinfunction "B3_13") (pintype "output"))
      (node (ref "RN1") (pin "2") (pinfunction "1_2") (pintype "passive"))
    )
    (net (code "75") (name "Net-(IC1-B4)") (class "Default")
      (node (ref "IC1") (pin "12") (pinfunction "B4_12") (pintype "output"))
      (node (ref "RN1") (pin "3") (pinfunction "1_3") (pintype "passive"))
    )
    (net (code "76") (name "Net-(IC2-BOOT)") (class "Default")
      (node (ref "C10") (pin "2") (pinfunction "2_2") (pintype "passive"))
      (node (ref "IC2") (pin "1") (pinfunction "BOOT_1") (pintype "output"))
    )
    (net (code "77") (name "Net-(IC2-COMP)") (class "Default")
      (node (ref "C16") (pin "2") (pinfunction "2_2") (pintype "passive"))
      (node (ref "IC2") (pin "8") (pinfunction "COMP_8") (pintype "output"))
      (node (ref "R9") (pin "2") (pinfunction "2_2") (pintype "passive"))
    )
    (net (code "78") (name "Net-(IC2-EN)") (class "Default")
      (node (ref "IC2") (pin "3") (pinfunction "EN_3") (pintype "input"))
      (node (ref "R3") (pin "1") (pinfunction "1_1") (pintype "passive"))
      (node (ref "R6") (pin "2") (pinfunction "2_2") (pintype "passive"))
    )
    (net (code "79") (name "Net-(IC2-PH)") (class "Default")
      (node (ref "C10") (pin "1") (pinfunction "1_1") (pintype "passive"))
      (node (ref "C11") (pin "1") (pinfunction "1_1") (pintype "passive"))
      (node (ref "D2") (pin "C") (pinfunction "C_C") (pintype "passive"))
      (node (ref "IC2") (pin "10") (pinfunction "PH_10") (pintype "input"))
      (node (ref "TR1") (pin "1") (pinfunction "1_1") (pintype "passive"))
    )
    (net (code "80") (name "Net-(IC2-RT{slash}CLK)") (class "Default")
      (node (ref "IC2") (pin "5") (pinfunction "RT/CLK_5") (pintype "input"))
      (node (ref "R8") (pin "2") (pinfunction "2_2") (pintype "passive"))
    )
    (net (code "81") (name "Net-(IC2-SS{slash}TR)") (class "Default")
      (node (ref "C15") (pin "1") (pinfunction "1_1") (pintype "passive"))
      (node (ref "IC2") (pin "4") (pinfunction "SS/TR_4") (pintype "input"))
    )
    (net (code "82") (name "Net-(IC2-VSENSE)") (class "Default")
      (node (ref "IC2") (pin "7") (pinfunction "VSENSE_7") (pintype "input"))
      (node (ref "R10") (pin "2") (pinfunction "2_2") (pintype "passive"))
      (node (ref "R7") (pin "1") (pinfunction "1_1") (pintype "passive"))
    )
    (net (code "83") (name "Net-(IC3-B1)") (class "Default")
      (node (ref "IC3") (pin "14") (pinfunction "B1_14") (pintype "output"))
      (node (ref "RN1") (pin "4") (pinfunction "1_4") (pintype "passive"))
    )
    (net (code "84") (name "Net-(IC5-BYPASS)") (class "Default")
      (node (ref "C23") (pin "2") (pinfunction "2_2") (pintype "passive"))
      (node (ref "IC5") (pin "4") (pinfunction "BYPASS_4") (pintype "passive"))
    )
    (net (code "85") (name "Net-(IC6A-O)") (class "Default")
      (node (ref "IC6") (pin "6") (pinfunction "O_6") (pintype "output"))
      (node (ref "R16") (pin "2") (pinfunction "2_2") (pintype "passive"))
    )
    (net (code "86") (name "Net-(IC6B-O)") (class "Default")
      (node (ref "IC6") (pin "4") (pinfunction "O_4") (pintype "output"))
      (node (ref "R18") (pin "2") (pinfunction "2_2") (pintype "passive"))
    )
    (net (code "87") (name "Net-(IC7-IO1)") (class "Default")
      (node (ref "IC7") (pin "1") (pinfunction "IO1_1") (pintype "bidirectional"))
      (node (ref "RN2") (pin "8") (pinfunction "2_8") (pintype "passive"))
      (node (ref "X3") (pin "6") (pinfunction "S_6") (pintype "passive"))
    )
    (net (code "88") (name "Net-(IC7-IO2)") (class "Default")
      (node (ref "IC7") (pin "2") (pinfunction "IO2_2") (pintype "bidirectional"))
      (node (ref "RN2") (pin "6") (pinfunction "2_6") (pintype "passive"))
      (node (ref "X3") (pin "5") (pinfunction "S_5") (pintype "passive"))
    )
    (net (code "89") (name "Net-(IC8-PB5)") (class "Default")
      (node (ref "IC8") (pin "41") (pinfunction "PB5_41") (pintype "bidirectional"))
      (node (ref "OE#2") (pin "1") (pinfunction "1_1") (pintype "passive"))
    )
    (net (code "90") (name "Net-(IC8-PB6)") (class "Default")
      (node (ref "IC8") (pin "42") (pinfunction "PB6_42") (pintype "bidirectional"))
      (node (ref "OE#1") (pin "1") (pinfunction "1_1") (pintype "passive"))
    )
    (net (code "91") (name "Net-(IC8-PF0-OSC_IN)") (class "Default")
      (node (ref "C32") (pin "2") (pinfunction "2_2") (pintype "passive"))
      (node (ref "IC8") (pin "5") (pinfunction "PF0-OSC_IN_5") (pintype "bidirectional"))
      (node (ref "Y1") (pin "3") (pinfunction "2_3") (pintype "passive"))
    )
    (net (code "92") (name "Net-(IC8-PF1-OSC_OUT)") (class "Default")
      (node (ref "C33") (pin "2") (pinfunction "2_2") (pintype "passive"))
      (node (ref "IC8") (pin "6") (pinfunction "PF1-OSC_OUT_6") (pintype "bidirectional"))
      (node (ref "Y1") (pin "1") (pinfunction "1_1") (pintype "passive"))
    )
    (net (code "93") (name "Net-(IC10A-+IN)") (class "Default")
      (node (ref "IC10") (pin "3") (pinfunction "+IN_3") (pintype "input"))
      (node (ref "R59") (pin "2") (pinfunction "2_2") (pintype "passive"))
      (node (ref "R60") (pin "2") (pinfunction "2_2") (pintype "passive"))
    )
    (net (code "94") (name "Net-(IC10A--IN)") (class "Default")
      (node (ref "C69") (pin "2") (pinfunction "2_2") (pintype "passive"))
      (node (ref "IC10") (pin "2") (pinfunction "-IN_2") (pintype "input"))
      (node (ref "R56") (pin "2") (pinfunction "2_2") (pintype "passive"))
      (node (ref "R57") (pin "1") (pinfunction "1_1") (pintype "passive"))
    )
    (net (code "95") (name "Net-(IC10A-OUT)") (class "Default")
      (node (ref "C69") (pin "1") (pinfunction "1_1") (pintype "passive"))
      (node (ref "IC10") (pin "1") (pinfunction "OUT_1") (pintype "output"))
      (node (ref "IC13") (pin "14") (pinfunction "CTRL1_14") (pintype "input"))
      (node (ref "R57") (pin "2") (pinfunction "2_2") (pintype "passive"))
    )
    (net (code "96") (name "Net-(IC10B-+IN)") (class "Default")
      (node (ref "IC10") (pin "5") (pinfunction "+IN_5") (pintype "input"))
      (node (ref "R33") (pin "2") (pinfunction "2_2") (pintype "passive"))
      (node (ref "R34") (pin "2") (pinfunction "2_2") (pintype "passive"))
    )
    (net (code "97") (name "Net-(IC10B--IN)") (class "Default")
      (node (ref "C48") (pin "2") (pinfunction "2_2") (pintype "passive"))
      (node (ref "IC10") (pin "6") (pinfunction "-IN_6") (pintype "input"))
      (node (ref "R30") (pin "2") (pinfunction "2_2") (pintype "passive"))
      (node (ref "R31") (pin "1") (pinfunction "1_1") (pintype "passive"))
    )
    (net (code "98") (name "Net-(IC10B-OUT)") (class "Default")
      (node (ref "C48") (pin "1") (pinfunction "1_1") (pintype "passive"))
      (node (ref "IC10") (pin "7") (pinfunction "OUT_7") (pintype "output"))
      (node (ref "IC11") (pin "14") (pinfunction "CTRL1_14") (pintype "input"))
      (node (ref "R31") (pin "2") (pinfunction "2_2") (pintype "passive"))
    )
    (net (code "99") (name "Net-(IC11-BG)") (class "Default")
      (node (ref "IC11") (pin "1") (pinfunction "BG_1") (pintype "output"))
      (node (ref "R38") (pin "1") (pinfunction "1_1") (pintype "passive"))
    )
    (net (code "100") (name "Net-(IC11-ISMON)") (class "Default")
      (node (ref "IC11") (pin "19") (pinfunction "ISMON_19") (pintype "output"))
      (node (ref "R40") (pin "2") (pinfunction "2_2") (pintype "passive"))
    )
    (net (code "101") (name "Net-(IC11-PWM)") (class "Default")
      (node (ref "IC11") (pin "22") (pinfunction "PWM_22") (pintype "input"))
      (node (ref "R45") (pin "2") (pinfunction "2_2") (pintype "passive"))
    )
    (net (code "102") (name "Net-(IC11-RT)") (class "Default")
      (node (ref "IC11") (pin "20") (pinfunction "RT_20") (pintype "input"))
      (node (ref "R44") (pin "2") (pinfunction "2_2") (pintype "passive"))
    )
    (net (code "103") (name "Net-(IC11-SENSE+)") (class "Default")
      (node (ref "C65") (pin "1") (pinfunction "1_1") (pintype "passive"))
      (node (ref "IC11") (pin "17") (pinfunction "SENSE+_17") (pintype "input"))
      (node (ref "R36") (pin "1") (pinfunction "1_1") (pintype "passive"))
    )
    (net (code "104") (name "Net-(IC11-SENSE-)") (class "Default")
      (node (ref "C65") (pin "2") (pinfunction "2_2") (pintype "passive"))
      (node (ref "IC11") (pin "16") (pinfunction "SENSE-_16") (pintype "input"))
      (node (ref "R37") (pin "1") (pinfunction "1_1") (pintype "passive"))
    )
    (net (code "105") (name "Net-(IC11-SS)") (class "Default")
      (node (ref "C66") (pin "2") (pinfunction "2_2") (pintype "passive"))
      (node (ref "IC11") (pin "15") (pinfunction "SS_15") (pintype "input"))
    )
    (net (code "106") (name "Net-(IC11-SW)") (class "Default")
      (node (ref "C54") (pin "2") (pinfunction "2_2") (pintype "passive"))
      (node (ref "C58") (pin "1") (pinfunction "1_1") (pintype "passive"))
      (node (ref "D5") (pin "C") (pinfunction "C_C") (pintype "passive"))
      (node (ref "IC11") (pin "26") (pinfunction "SW_26") (pintype "output"))
      (node (ref "L2") (pin "1") (pinfunction "1_1") (pintype "passive"))
      (node (ref "Q2") (pin "3") (pinfunction "S_3") (pintype "passive"))
      (node (ref "Q3") (pin "2") (pinfunction "D_2") (pintype "passive"))
    )
    (net (code "107") (name "Net-(IC11-TG)") (class "Default")
      (node (ref "IC11") (pin "25") (pinfunction "TG_25") (pintype "output"))
      (node (ref "R32") (pin "1") (pinfunction "1_1") (pintype "passive"))
    )
    (net (code "108") (name "Net-(IC11-VC)") (class "Default")
      (node (ref "C67") (pin "2") (pinfunction "2_2") (pintype "passive"))
      (node (ref "IC11") (pin "18") (pinfunction "VC_18") (pintype "passive"))
    )
    (net (code "109") (name "Net-(IC11-~{FAULT})") (class "Default")
      (node (ref "IC11") (pin "9") (pinfunction "~{FAULT}_9") (pintype "output"))
      (node (ref "R46") (pin "1") (pinfunction "1_1") (pintype "passive"))
    )
    (net (code "110") (name "Net-(IC12A-+IN)") (class "Default")
      (node (ref "IC12") (pin "3") (pinfunction "+IN_3") (pintype "input"))
      (node (ref "R78") (pin "1") (pinfunction "1_1") (pintype "passive"))
      (node (ref "R79") (pin "2") (pinfunction "2_2") (pintype "passive"))
    )
    (net (code "111") (name "Net-(IC12A--IN)") (class "Default")
      (node (ref "IC12") (pin "13") (pinfunction "-IN_13") (pintype "input"))
      (node (ref "IC12") (pin "14") (pinfunction "OUT_14") (pintype "output"))
      (node (ref "IC12") (pin "2") (pinfunction "-IN_2") (pintype "input"))
    )
    (net (code "112") (name "Net-(IC12B-+IN)") (class "Default")
      (node (ref "IC12") (pin "5") (pinfunction "+IN_5") (pintype "input"))
      (node (ref "R52") (pin "1") (pinfunction "1_1") (pintype "passive"))
      (node (ref "R53") (pin "2") (pinfunction "2_2") (pintype "passive"))
    )
    (net (code "113") (name "Net-(IC12B--IN)") (class "Default")
      (node (ref "IC12") (pin "6") (pinfunction "-IN_6") (pintype "input"))
      (node (ref "IC12") (pin "8") (pinfunction "OUT_8") (pintype "output"))
      (node (ref "IC12") (pin "9") (pinfunction "-IN_9") (pintype "input"))
    )
    (net (code "114") (name "Net-(IC13-BG)") (class "Default")
      (node (ref "IC13") (pin "1") (pinfunction "BG_1") (pintype "output"))
      (node (ref "R64") (pin "1") (pinfunction "1_1") (pintype "passive"))
    )
    (net (code "115") (name "Net-(IC13-ISMON)") (class "Default")
      (node (ref "IC13") (pin "19") (pinfunction "ISMON_19") (pintype "output"))
      (node (ref "R66") (pin "2") (pinfunction "2_2") (pintype "passive"))
    )
    (net (code "116") (name "Net-(IC13-PWM)") (class "Default")
      (node (ref "IC13") (pin "22") (pinfunction "PWM_22") (pintype "input"))
      (node (ref "R71") (pin "2") (pinfunction "2_2") (pintype "passive"))
    )
    (net (code "117") (name "Net-(IC13-RT)") (class "Default")
      (node (ref "IC13") (pin "20") (pinfunction "RT_20") (pintype "input"))
      (node (ref "R70") (pin "2") (pinfunction "2_2") (pintype "passive"))
    )
    (net (code "118") (name "Net-(IC13-SENSE+)") (class "Default")
      (node (ref "C85") (pin "1") (pinfunction "1_1") (pintype "passive"))
      (node (ref "IC13") (pin "17") (pinfunction "SENSE+_17") (pintype "input"))
      (node (ref "R62") (pin "1") (pinfunction "1_1") (pintype "passive"))
    )
    (net (code "119") (name "Net-(IC13-SENSE-)") (class "Default")
      (node (ref "C85") (pin "2") (pinfunction "2_2") (pintype "passive"))
      (node (ref "IC13") (pin "16") (pinfunction "SENSE-_16") (pintype "input"))
      (node (ref "R63") (pin "1") (pinfunction "1_1") (pintype "passive"))
    )
    (net (code "120") (name "Net-(IC13-SS)") (class "Default")
      (node (ref "C86") (pin "2") (pinfunction "2_2") (pintype "passive"))
      (node (ref "IC13") (pin "15") (pinfunction "SS_15") (pintype "input"))
    )
    (net (code "121") (name "Net-(IC13-SW)") (class "Default")
      (node (ref "C74") (pin "2") (pinfunction "2_2") (pintype "passive"))
      (node (ref "C78") (pin "1") (pinfunction "1_1") (pintype "passive"))
      (node (ref "D8") (pin "C") (pinfunction "C_C") (pintype "passive"))
      (node (ref "IC13") (pin "26") (pinfunction "SW_26") (pintype "output"))
      (node (ref "L4") (pin "1") (pinfunction "1_1") (pintype "passive"))
      (node (ref "Q7") (pin "3") (pinfunction "S_3") (pintype "passive"))
      (node (ref "Q8") (pin "2") (pinfunction "D_2") (pintype "passive"))
    )
    (net (code "122") (name "Net-(IC13-TG)") (class "Default")
      (node (ref "IC13") (pin "25") (pinfunction "TG_25") (pintype "output"))
      (node (ref "R58") (pin "1") (pinfunction "1_1") (pintype "passive"))
    )
    (net (code "123") (name "Net-(IC13-VC)") (class "Default")
      (node (ref "C87") (pin "2") (pinfunction "2_2") (pintype "passive"))
      (node (ref "IC13") (pin "18") (pinfunction "VC_18") (pintype "passive"))
    )
    (net (code "124") (name "Net-(IC13-~{FAULT})") (class "Default")
      (node (ref "IC13") (pin "9") (pinfunction "~{FAULT}_9") (pintype "output"))
      (node (ref "R72") (pin "1") (pinfunction "1_1") (pintype "passive"))
    )
    (net (code "125") (name "Net-(L1A-1)") (class "Default")
      (node (ref "C1") (pin "2") (pinfunction "2_2") (pintype "passive"))
      (node (ref "L1") (pin "3") (pinfunction "1_3") (pintype "passive"))
      (node (ref "R1") (pin "2") (pinfunction "2_2") (pintype "passive"))
      (node (ref "X1") (pin "1") (pinfunction "1_1") (pintype "passive"))
    )
    (net (code "126") (name "Net-(L2-Pad2)") (class "Default")
      (node (ref "L2") (pin "2") (pinfunction "2_2") (pintype "passive"))
      (node (ref "R35") (pin "1") (pinfunction "1_1") (pintype "passive"))
    )
    (net (code "127") (name "Net-(L4-Pad2)") (class "Default")
      (node (ref "L4") (pin "2") (pinfunction "2_2") (pintype "passive"))
      (node (ref "R61") (pin "1") (pinfunction "1_1") (pintype "passive"))
    )
    (net (code "128") (name "Net-(LED1-AG)") (class "Default")
      (node (ref "LED1") (pin "GREEN") (pinfunction "AG_GREEN") (pintype "passive"))
      (node (ref "Q4") (pin "2") (pinfunction "S_2") (pintype "passive"))
    )
    (net (code "129") (name "Net-(LED1-AR)") (class "Default")
      (node (ref "LED1") (pin "RED") (pinfunction "AR_RED") (pintype "passive"))
      (node (ref "R51") (pin "1") (pinfunction "1_1") (pintype "passive"))
    )
    (net (code "130") (name "Net-(LED2-AG)") (class "Default")
      (node (ref "LED2") (pin "GREEN") (pinfunction "AG_GREEN") (pintype "passive"))
      (node (ref "Q9") (pin "2") (pinfunction "S_2") (pintype "passive"))
    )
    (net (code "131") (name "Net-(LED2-AR)") (class "Default")
      (node (ref "LED2") (pin "RED") (pinfunction "AR_RED") (pintype "passive"))
      (node (ref "R77") (pin "1") (pinfunction "1_1") (pintype "passive"))
    )
    (net (code "132") (name "Net-(Q1-D-Pad2)") (class "Default")
      (node (ref "Q1") (pin "2") (pinfunction "D_2") (pintype "passive"))
      (node (ref "Q1") (pin "4") (pinfunction "D_4") (pintype "passive"))
      (node (ref "R28") (pin "2") (pinfunction "2_2") (pintype "passive"))
    )
    (net (code "133") (name "Net-(Q2-G)") (class "Default")
      (node (ref "Q2") (pin "1") (pinfunction "G_1") (pintype "passive"))
      (node (ref "R32") (pin "2") (pinfunction "2_2") (pintype "passive"))
    )
    (net (code "134") (name "Net-(Q3-G)") (class "Default")
      (node (ref "Q3") (pin "1") (pinfunction "G_1") (pintype "passive"))
      (node (ref "R38") (pin "2") (pinfunction "2_2") (pintype "passive"))
    )
    (net (code "135") (name "Net-(Q4-D)") (class "Default")
      (node (ref "Q4") (pin "3") (pinfunction "D_3") (pintype "passive"))
      (node (ref "Q5") (pin "3") (pinfunction "D_3") (pintype "passive"))
    )
    (net (code "136") (name "Net-(Q6-D-Pad2)") (class "Default")
      (node (ref "Q6") (pin "2") (pinfunction "D_2") (pintype "passive"))
      (node (ref "Q6") (pin "4") (pinfunction "D_4") (pintype "passive"))
      (node (ref "R54") (pin "2") (pinfunction "2_2") (pintype "passive"))
    )
    (net (code "137") (name "Net-(Q7-G)") (class "Default")
      (node (ref "Q7") (pin "1") (pinfunction "G_1") (pintype "passive"))
      (node (ref "R58") (pin "2") (pinfunction "2_2") (pintype "passive"))
    )
    (net (code "138") (name "Net-(Q8-G)") (class "Default")
      (node (ref "Q8") (pin "1") (pinfunction "G_1") (pintype "passive"))
      (node (ref "R64") (pin "2") (pinfunction "2_2") (pintype "passive"))
    )
    (net (code "139") (name "Net-(Q10-D)") (class "Default")
      (node (ref "Q10") (pin "3") (pinfunction "D_3") (pintype "passive"))
      (node (ref "Q9") (pin "3") (pinfunction "D_3") (pintype "passive"))
    )
    (net (code "140") (name "Net-(R35-Pad1S)") (class "Default")
      (node (ref "R35") (pin "1S") (pinfunction "1S_1S") (pintype "passive"))
      (node (ref "R36") (pin "2") (pinfunction "2_2") (pintype "passive"))
    )
    (net (code "141") (name "Net-(R35-Pad2S)") (class "Default")
      (node (ref "R35") (pin "2S") (pinfunction "2S_2S") (pintype "passive"))
      (node (ref "R37") (pin "2") (pinfunction "2_2") (pintype "passive"))
    )
    (net (code "142") (name "Net-(R61-Pad1S)") (class "Default")
      (node (ref "R61") (pin "1S") (pinfunction "1S_1S") (pintype "passive"))
      (node (ref "R62") (pin "2") (pinfunction "2_2") (pintype "passive"))
    )
    (net (code "143") (name "Net-(R61-Pad2S)") (class "Default")
      (node (ref "R61") (pin "2S") (pinfunction "2S_2S") (pintype "passive"))
      (node (ref "R63") (pin "2") (pinfunction "2_2") (pintype "passive"))
    )
    (net (code "144") (name "Net-(X1B-1)") (class "Default")
      (node (ref "C1") (pin "1") (pinfunction "1_1") (pintype "passive"))
      (node (ref "L1") (pin "1") (pinfunction "1_1") (pintype "passive"))
      (node (ref "R1") (pin "1") (pinfunction "1_1") (pintype "passive"))
      (node (ref "X1") (pin "2") (pinfunction "1_2") (pintype "passive"))
    )
    (net (code "145") (name "Net-(X3A-S)") (class "Default")
      (node (ref "JP2") (pin "2") (pinfunction "2_2") (pintype "passive"))
      (node (ref "R19") (pin "2") (pinfunction "2_2") (pintype "passive"))
      (node (ref "X3") (pin "1") (pinfunction "S_1") (pintype "passive"))
    )
    (net (code "146") (name "OE#1") (class "Default")
      (node (ref "IC11") (pin "4") (pinfunction "EV/UVLO_4") (pintype "input"))
      (node (ref "OE#2") (pin "2") (pinfunction "2_2") (pintype "passive"))
      (node (ref "Q4") (pin "1") (pinfunction "G_1") (pintype "passive"))
    )
    (net (code "147") (name "OE#2") (class "Default")
      (node (ref "IC13") (pin "4") (pinfunction "EV/UVLO_4") (pintype "input"))
      (node (ref "OE#1") (pin "2") (pinfunction "2_2") (pintype "passive"))
      (node (ref "Q9") (pin "1") (pinfunction "G_1") (pintype "passive"))
    )
    (net (code "148") (name "OE_SYNC") (class "Default")
      (node (ref "IC8") (pin "36") (pinfunction "PF7_36") (pintype "bidirectional"))
      (node (ref "RN1") (pin "8") (pinfunction "2_8") (pintype "passive"))
    )
    (net (code "149") (name "PE") (class "Default")
      (node (ref "C2") (pin "2") (pinfunction "2_2") (pintype "passive"))
      (node (ref "C3") (pin "1") (pinfunction "1_1") (pintype "passive"))
      (node (ref "C56") (pin "1") (pinfunction "1_1") (pintype "passive"))
      (node (ref "C63") (pin "1") (pinfunction "1_1") (pintype "passive"))
      (node (ref "C76") (pin "1") (pinfunction "1_1") (pintype "passive"))
      (node (ref "C83") (pin "1") (pinfunction "1_1") (pintype "passive"))
      (node (ref "J1") (pin "1") (pinfunction "P$1_1") (pintype "bidirectional"))
      (node (ref "J1") (pin "2") (pinfunction "P$1_2") (pintype "bidirectional"))
    )
    (net (code "150") (name "PWRGOOD") (class "Default")
      (node (ref "IC2") (pin "6") (pinfunction "PWRGD_6") (pintype "output"))
      (node (ref "IC8") (pin "40") (pinfunction "PB4_40") (pintype "bidirectional"))
    )
    (net (code "151") (name "SCLK") (class "Default")
      (node (ref "IC8") (pin "29") (pinfunction "PA8_29") (pintype "bidirectional"))
      (node (ref "RN1") (pin "7") (pinfunction "2_7") (pintype "passive"))
    )
    (net (code "152") (name "SWCLK") (class "Default")
      (node (ref "IC8") (pin "37") (pinfunction "PA14_37") (pintype "bidirectional"))
      (node (ref "RN2") (pin "2") (pinfunction "1_2") (pintype "passive"))
    )
    (net (code "153") (name "SWDIO") (class "Default")
      (node (ref "IC8") (pin "34") (pinfunction "PA13_34") (pintype "bidirectional"))
      (node (ref "RN2") (pin "4") (pinfunction "1_4") (pintype "passive"))
    )
    (net (code "154") (name "SWO") (class "Default")
      (node (ref "IC8") (pin "39") (pinfunction "PB3_39") (pintype "bidirectional"))
      (node (ref "RN2") (pin "1") (pinfunction "1_1") (pintype "passive"))
    )
    (net (code "155") (name "TCK") (class "Default")
      (node (ref "IC7") (pin "5") (pinfunction "IO4_5") (pintype "bidirectional"))
      (node (ref "RN2") (pin "7") (pinfunction "2_7") (pintype "passive"))
      (node (ref "X3") (pin "2") (pinfunction "S_2") (pintype "passive"))
    )
    (net (code "156") (name "TEMP#1") (class "Default")
      (node (ref "C34") (pin "2") (pinfunction "2_2") (pintype "passive"))
      (node (ref "IC8") (pin "10") (pinfunction "PA0_10") (pintype "bidirectional"))
      (node (ref "NTC1") (pin "2") (pinfunction "P$2_2") (pintype "bidirectional"))
      (node (ref "R21") (pin "1") (pinfunction "1_1") (pintype "passive"))
    )
    (net (code "157") (name "TEMP#2") (class "Default")
      (node (ref "C35") (pin "2") (pinfunction "2_2") (pintype "passive"))
      (node (ref "IC8") (pin "14") (pinfunction "PA4_14") (pintype "bidirectional"))
      (node (ref "NTC2") (pin "2") (pinfunction "P$2_2") (pintype "bidirectional"))
      (node (ref "R22") (pin "1") (pinfunction "1_1") (pintype "passive"))
    )
    (net (code "158") (name "TMS") (class "Default")
      (node (ref "IC7") (pin "4") (pinfunction "IO3_4") (pintype "bidirectional"))
      (node (ref "RN2") (pin "5") (pinfunction "2_5") (pintype "passive"))
      (node (ref "X3") (pin "4") (pinfunction "S_4") (pintype "passive"))
    )
    (net (code "159") (name "UART_RX") (class "Default")
      (node (ref "IC3") (pin "12") (pinfunction "B3_12") (pintype "output"))
      (node (ref "IC8") (pin "13") (pinfunction "PA3_13") (pintype "bidirectional"))
    )
    (net (code "160") (name "UART_TX") (class "Default")
      (node (ref "IC3") (pin "11") (pinfunction "B4_11") (pintype "input"))
      (node (ref "IC8") (pin "12") (pinfunction "PA2_12") (pintype "bidirectional"))
    )
    (net (code "161") (name "U_MON#1") (class "Default")
      (node (ref "C41") (pin "2") (pinfunction "2_2") (pintype "passive"))
      (node (ref "IC8") (pin "18") (pinfunction "PB0_18") (pintype "bidirectional"))
      (node (ref "R24") (pin "1") (pinfunction "1_1") (pintype "passive"))
    )
    (net (code "162") (name "U_MON#2") (class "Default")
      (node (ref "C43") (pin "2") (pinfunction "2_2") (pintype "passive"))
      (node (ref "IC8") (pin "20") (pinfunction "PB2_20") (pintype "bidirectional"))
      (node (ref "R26") (pin "1") (pinfunction "1_1") (pintype "passive"))
    )
    (net (code "163") (name "U_MON1") (class "Default")
      (node (ref "R24") (pin "2") (pinfunction "2_2") (pintype "passive"))
      (node (ref "R42") (pin "1") (pinfunction "1_1") (pintype "passive"))
      (node (ref "R49") (pin "2") (pinfunction "2_2") (pintype "passive"))
    )
    (net (code "164") (name "U_MON2") (class "Default")
      (node (ref "R26") (pin "2") (pinfunction "2_2") (pintype "passive"))
      (node (ref "R68") (pin "1") (pinfunction "1_1") (pintype "passive"))
      (node (ref "R75") (pin "2") (pinfunction "2_2") (pintype "passive"))
    )
    (net (code "165") (name "U_SET#1") (class "Default")
      (node (ref "R50") (pin "1") (pinfunction "1_1") (pintype "passive"))
      (node (ref "U_SET1") (pin "1") (pinfunction "1_1") (pintype "passive"))
    )
    (net (code "166") (name "U_SET#2") (class "Default")
      (node (ref "R76") (pin "1") (pinfunction "1_1") (pintype "passive"))
      (node (ref "U_SET2") (pin "1") (pinfunction "1_1") (pintype "passive"))
    )
    (net (code "167") (name "U_SET_OUT#1") (class "Default")
      (node (ref "IC8") (pin "16") (pinfunction "PA6_16") (pintype "bidirectional"))
      (node (ref "U_SET1") (pin "2") (pinfunction "2_2") (pintype "passive"))
    )
    (net (code "168") (name "U_SET_OUT#2") (class "Default")
      (node (ref "IC8") (pin "15") (pinfunction "PA5_15") (pintype "bidirectional"))
      (node (ref "U_SET2") (pin "2") (pinfunction "2_2") (pintype "passive"))
    )
    (net (code "169") (name "V+") (class "Default")
      (node (ref "C17") (pin "1") (pinfunction "1_1") (pintype "passive"))
      (node (ref "C20") (pin "2") (pinfunction "2_2") (pintype "passive"))
      (node (ref "C7") (pin "1") (pinfunction "1_1") (pintype "passive"))
      (node (ref "IC1") (pin "1") (pinfunction "VDD1_1") (pintype "passive"))
      (node (ref "IC3") (pin "1") (pinfunction "VDD1_1") (pintype "passive"))
      (node (ref "IC3") (pin "7") (pinfunction "EN1_7") (pintype "input"))
      (node (ref "IC4") (pin "8") (pinfunction "VCC_8") (pintype "power_in"))
      (node (ref "R11") (pin "1") (pinfunction "1_1") (pintype "passive"))
      (node (ref "R12") (pin "1") (pinfunction "1_1") (pintype "passive"))
      (node (ref "R13") (pin "1") (pinfunction "1_1") (pintype "passive"))
      (node (ref "X2") (pin "1") (pinfunction "1_1") (pintype "passive"))
    )
    (net (code "170") (name "VDDA") (class "Default")
      (node (ref "C37") (pin "2") (pinfunction "2_2") (pintype "passive"))
      (node (ref "C38") (pin "2") (pinfunction "2_2") (pintype "passive"))
      (node (ref "FB1") (pin "P$2") (pinfunction "2_P$2") (pintype "passive"))
      (node (ref "IC8") (pin "24") (pinfunction "VDDSD_24") (pintype "passive"))
      (node (ref "IC8") (pin "9") (pinfunction "VDDA/VREF+_9") (pintype "passive"))
    )
    (net (code "171") (name "VOUT1+") (class "Default")
      (node (ref "C59") (pin "1") (pinfunction "1_1") (pintype "passive"))
      (node (ref "C60") (pin "1") (pinfunction "1_1") (pintype "passive"))
      (node (ref "C62") (pin "+") (pinfunction "+_+") (pintype "passive"))
      (node (ref "L3") (pin "1") (pinfunction "1_1") (pintype "passive"))
      (node (ref "R35") (pin "2") (pinfunction "2_2") (pintype "passive"))
      (node (ref "R41") (pin "2") (pinfunction "2_2") (pintype "passive"))
      (node (ref "R42") (pin "2") (pinfunction "2_2") (pintype "passive"))
      (node (ref "ZD2") (pin "A") (pinfunction "A_A") (pintype "passive"))
    )
    (net (code "172") (name "VOUT2+") (class "Default")
      (node (ref "C79") (pin "1") (pinfunction "1_1") (pintype "passive"))
      (node (ref "C80") (pin "1") (pinfunction "1_1") (pintype "passive"))
      (node (ref "C82") (pin "+") (pinfunction "+_+") (pintype "passive"))
      (node (ref "L5") (pin "1") (pinfunction "1_1") (pintype "passive"))
      (node (ref "R61") (pin "2") (pinfunction "2_2") (pintype "passive"))
      (node (ref "R67") (pin "2") (pinfunction "2_2") (pintype "passive"))
      (node (ref "R68") (pin "2") (pinfunction "2_2") (pintype "passive"))
      (node (ref "ZD4") (pin "A") (pinfunction "A_A") (pintype "passive"))
    )
    (net (code "173") (name "VOUT_LC1+") (class "Default")
      (node (ref "C56") (pin "2") (pinfunction "2_2") (pintype "passive"))
      (node (ref "C57") (pin "1") (pinfunction "1_1") (pintype "passive"))
      (node (ref "C61") (pin "1") (pinfunction "+_1") (pintype "passive"))
      (node (ref "CH1") (pin "TIP") (pinfunction "TIP_TIP") (pintype "bidirectional"))
      (node (ref "J2") (pin "1") (pinfunction "1_1") (pintype "passive"))
      (node (ref "J2") (pin "1.1") (pinfunction "1_1.1") (pintype "passive"))
      (node (ref "L3") (pin "2") (pinfunction "2_2") (pintype "passive"))
      (node (ref "R43") (pin "1") (pinfunction "1_1") (pintype "passive"))
      (node (ref "ZD3") (pin "C") (pinfunction "C_C") (pintype "passive"))
    )
    (net (code "174") (name "VOUT_LC2+") (class "Default")
      (node (ref "C76") (pin "2") (pinfunction "2_2") (pintype "passive"))
      (node (ref "C77") (pin "1") (pinfunction "1_1") (pintype "passive"))
      (node (ref "C81") (pin "1") (pinfunction "+_1") (pintype "passive"))
      (node (ref "CH2") (pin "TIP") (pinfunction "TIP_TIP") (pintype "bidirectional"))
      (node (ref "J4") (pin "1") (pinfunction "1_1") (pintype "passive"))
      (node (ref "J4") (pin "1.1") (pinfunction "1_1.1") (pintype "passive"))
      (node (ref "L5") (pin "2") (pinfunction "2_2") (pintype "passive"))
      (node (ref "R69") (pin "1") (pinfunction "1_1") (pintype "passive"))
      (node (ref "ZD5") (pin "C") (pinfunction "C_C") (pintype "passive"))
    )
    (net (code "175") (name "VREF1") (class "Default")
      (node (ref "C53") (pin "1") (pinfunction "1_1") (pintype "passive"))
      (node (ref "IC11") (pin "10") (pinfunction "FBIN_10") (pintype "input"))
      (node (ref "IC11") (pin "13") (pinfunction "CTRL2_13") (pintype "input"))
      (node (ref "IC11") (pin "5") (pinfunction "VREF_5") (pintype "output"))
      (node (ref "R52") (pin "2") (pinfunction "2_2") (pintype "passive"))
    )
    (net (code "176") (name "VREF2") (class "Default")
      (node (ref "C73") (pin "1") (pinfunction "1_1") (pintype "passive"))
      (node (ref "IC13") (pin "10") (pinfunction "FBIN_10") (pintype "input"))
      (node (ref "IC13") (pin "13") (pinfunction "CTRL2_13") (pintype "input"))
      (node (ref "IC13") (pin "5") (pinfunction "VREF_5") (pintype "output"))
      (node (ref "R78") (pin "2") (pinfunction "2_2") (pintype "passive"))
    )
    (net (code "177") (name "unconnected-(IC8-PA15-Pad38)") (class "Default")
      (node (ref "IC8") (pin "38") (pinfunction "PA15_38") (pintype "bidirectional"))
    )
    (net (code "178") (name "unconnected-(IC8-PB7-Pad43)") (class "Default")
      (node (ref "IC8") (pin "43") (pinfunction "PB7_43") (pintype "bidirectional"))
    )
    (net (code "179") (name "unconnected-(IC8-PB14-Pad26)") (class "Default")
      (node (ref "IC8") (pin "26") (pinfunction "PB14_26") (pintype "bidirectional"))
    )
    (net (code "180") (name "unconnected-(IC8-PB15-Pad27)") (class "Default")
      (node (ref "IC8") (pin "27") (pinfunction "PB15_27") (pintype "bidirectional"))
    )
    (net (code "181") (name "unconnected-(IC8-PD8-Pad28)") (class "Default")
      (node (ref "IC8") (pin "28") (pinfunction "PD8_28") (pintype "bidirectional"))
    )
    (net (code "182") (name "unconnected-(IC8-PE9-Pad22)") (class "Default")
      (node (ref "IC8") (pin "22") (pinfunction "PE9_22") (pintype "bidirectional"))
    )
    (net (code "183") (name "unconnected-(IC8-PF6-Pad35)") (class "Default")
      (node (ref "IC8") (pin "35") (pinfunction "PF6_35") (pintype "bidirectional"))
    )
    (net (code "184") (name "unconnected-(IC8-VBAT-Pad1)") (class "Default")
      (node (ref "IC8") (pin "1") (pinfunction "VBAT_1") (pintype "passive"))
    )
    (net (code "185") (name "unconnected-(IC11-IVINMON-Pad8)") (class "Default")
      (node (ref "IC11") (pin "8") (pinfunction "IVINMON_8") (pintype "output"))
    )
    (net (code "186") (name "unconnected-(IC11-PWMOUT-Pad24)") (class "Default")
      (node (ref "IC11") (pin "24") (pinfunction "PWMOUT_24") (pintype "output"))
    )
    (net (code "187") (name "unconnected-(IC13-IVINMON-Pad8)") (class "Default")
      (node (ref "IC13") (pin "8") (pinfunction "IVINMON_8") (pintype "output"))
    )
    (net (code "188") (name "unconnected-(IC13-PWMOUT-Pad24)") (class "Default")
      (node (ref "IC13") (pin "24") (pinfunction "PWMOUT_24") (pintype "output"))
    )
    (net (code "189") (name "~{RESET}") (class "Default")
      (node (ref "IC1") (pin "15") (pinfunction "B1_15") (pintype "output"))
      (node (ref "JP3") (pin "1") (pinfunction "1_1") (pintype "passive"))
    )
  )
)
